# Tay_Cam.net
KiCad netlist of a schematic drawn in Altium Designer
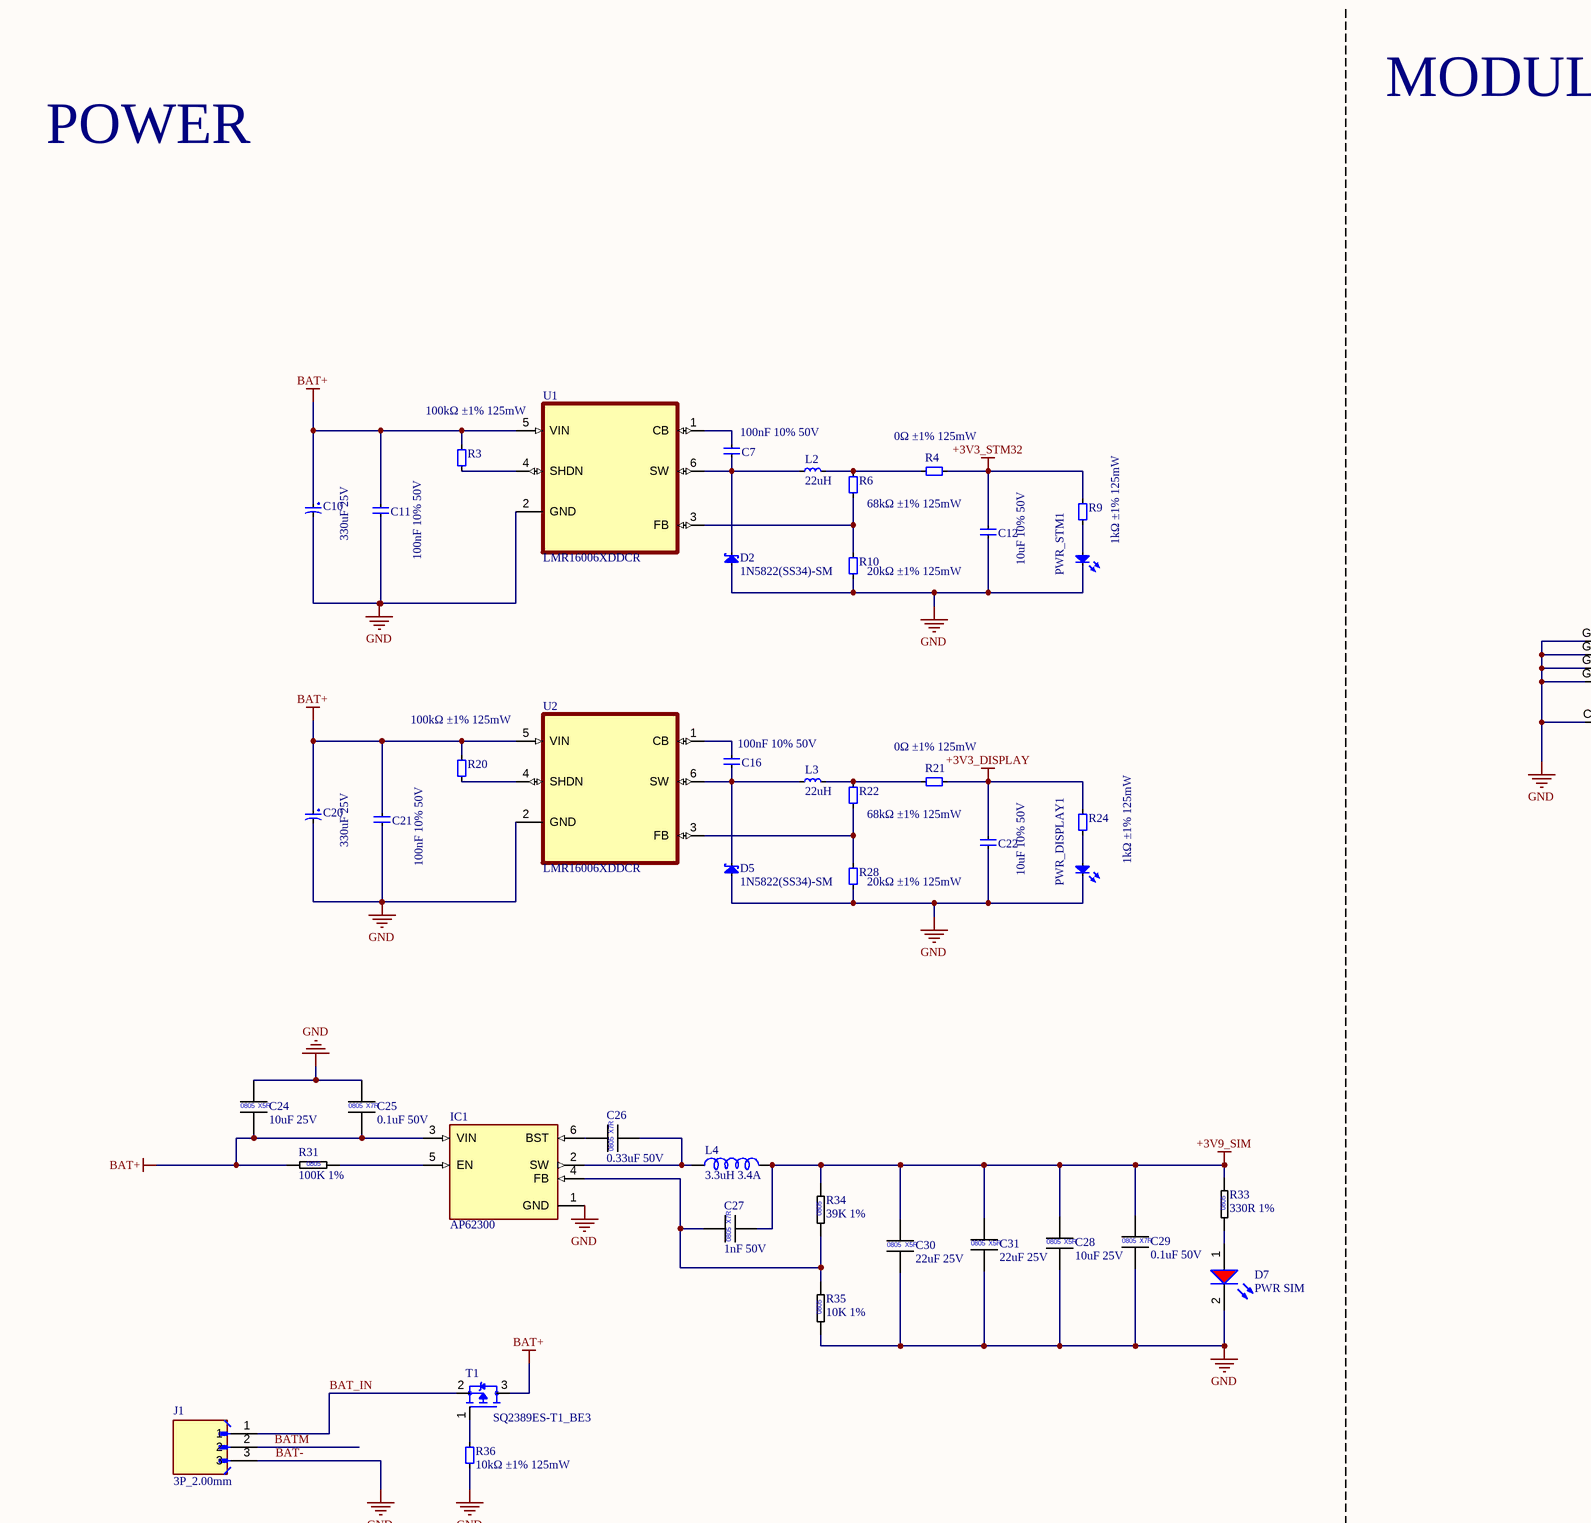
[diagram p0: Tay_Cam.SchDoc, top column 1 of 4]
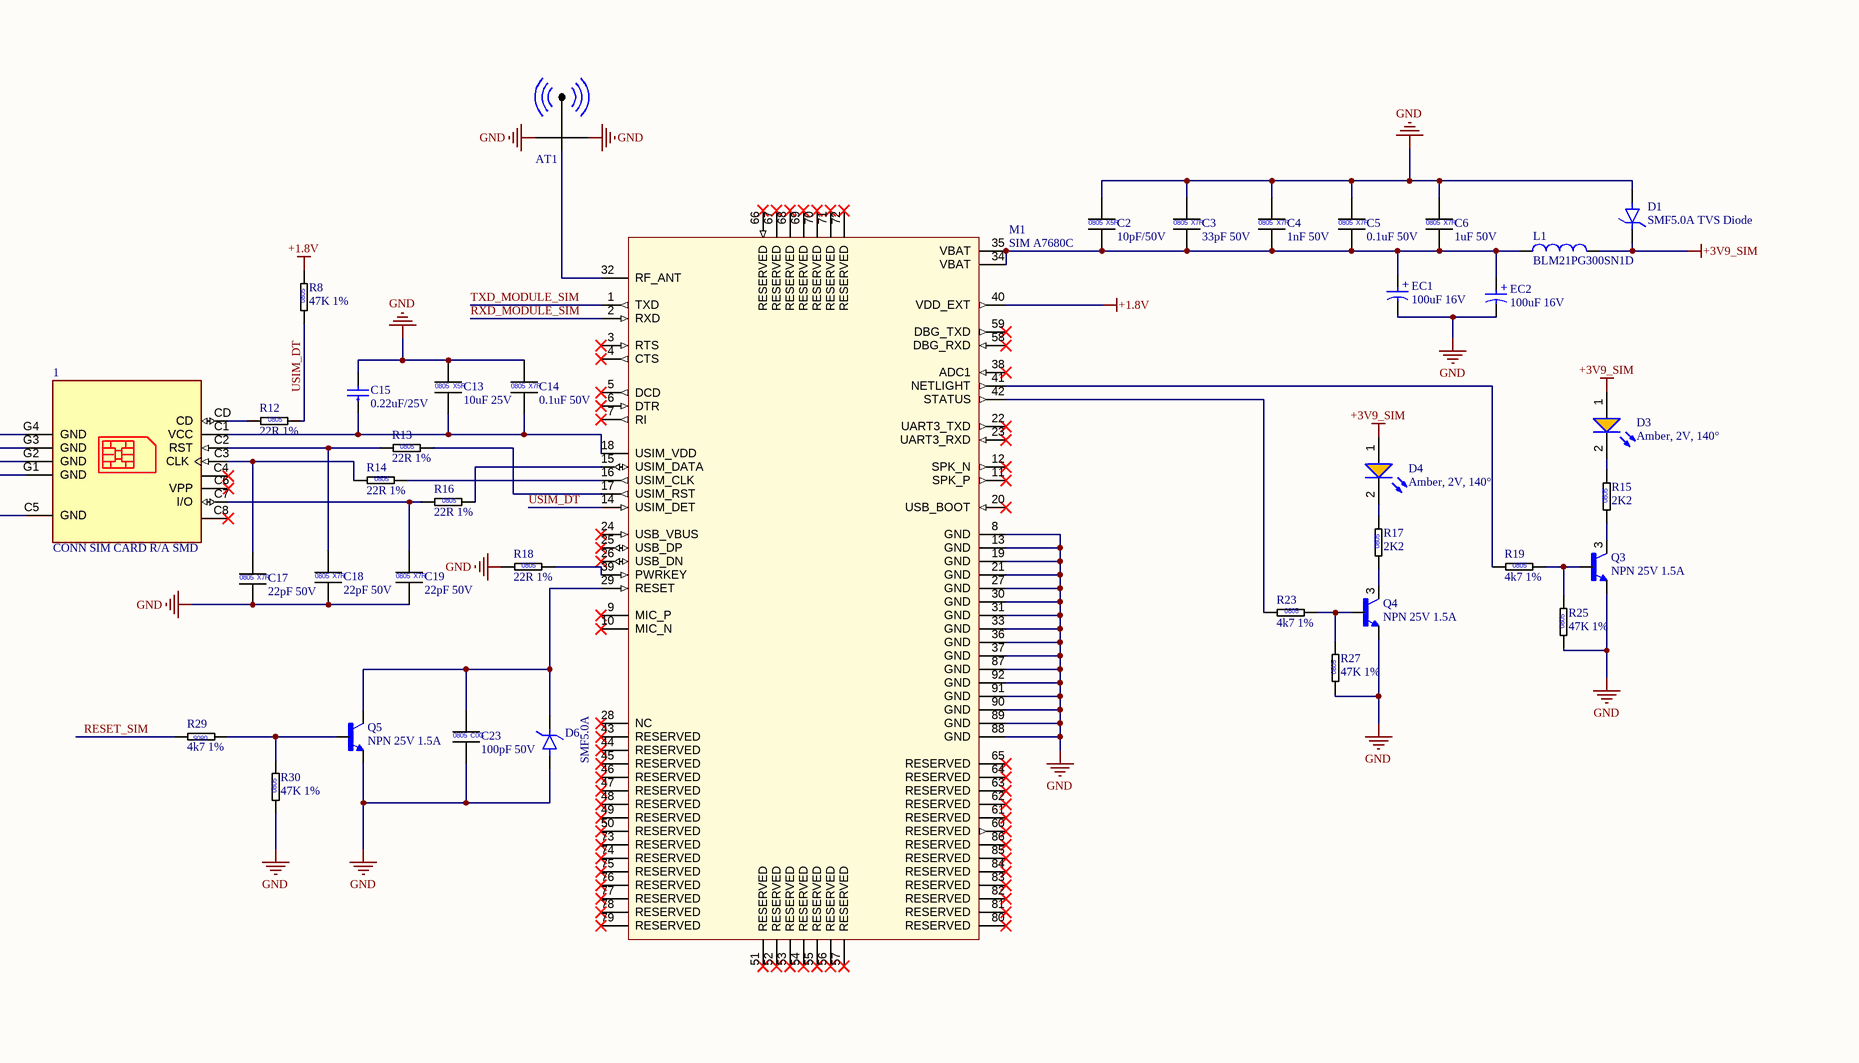
[diagram p1: Tay_Cam.SchDoc, top column 2 of 4]
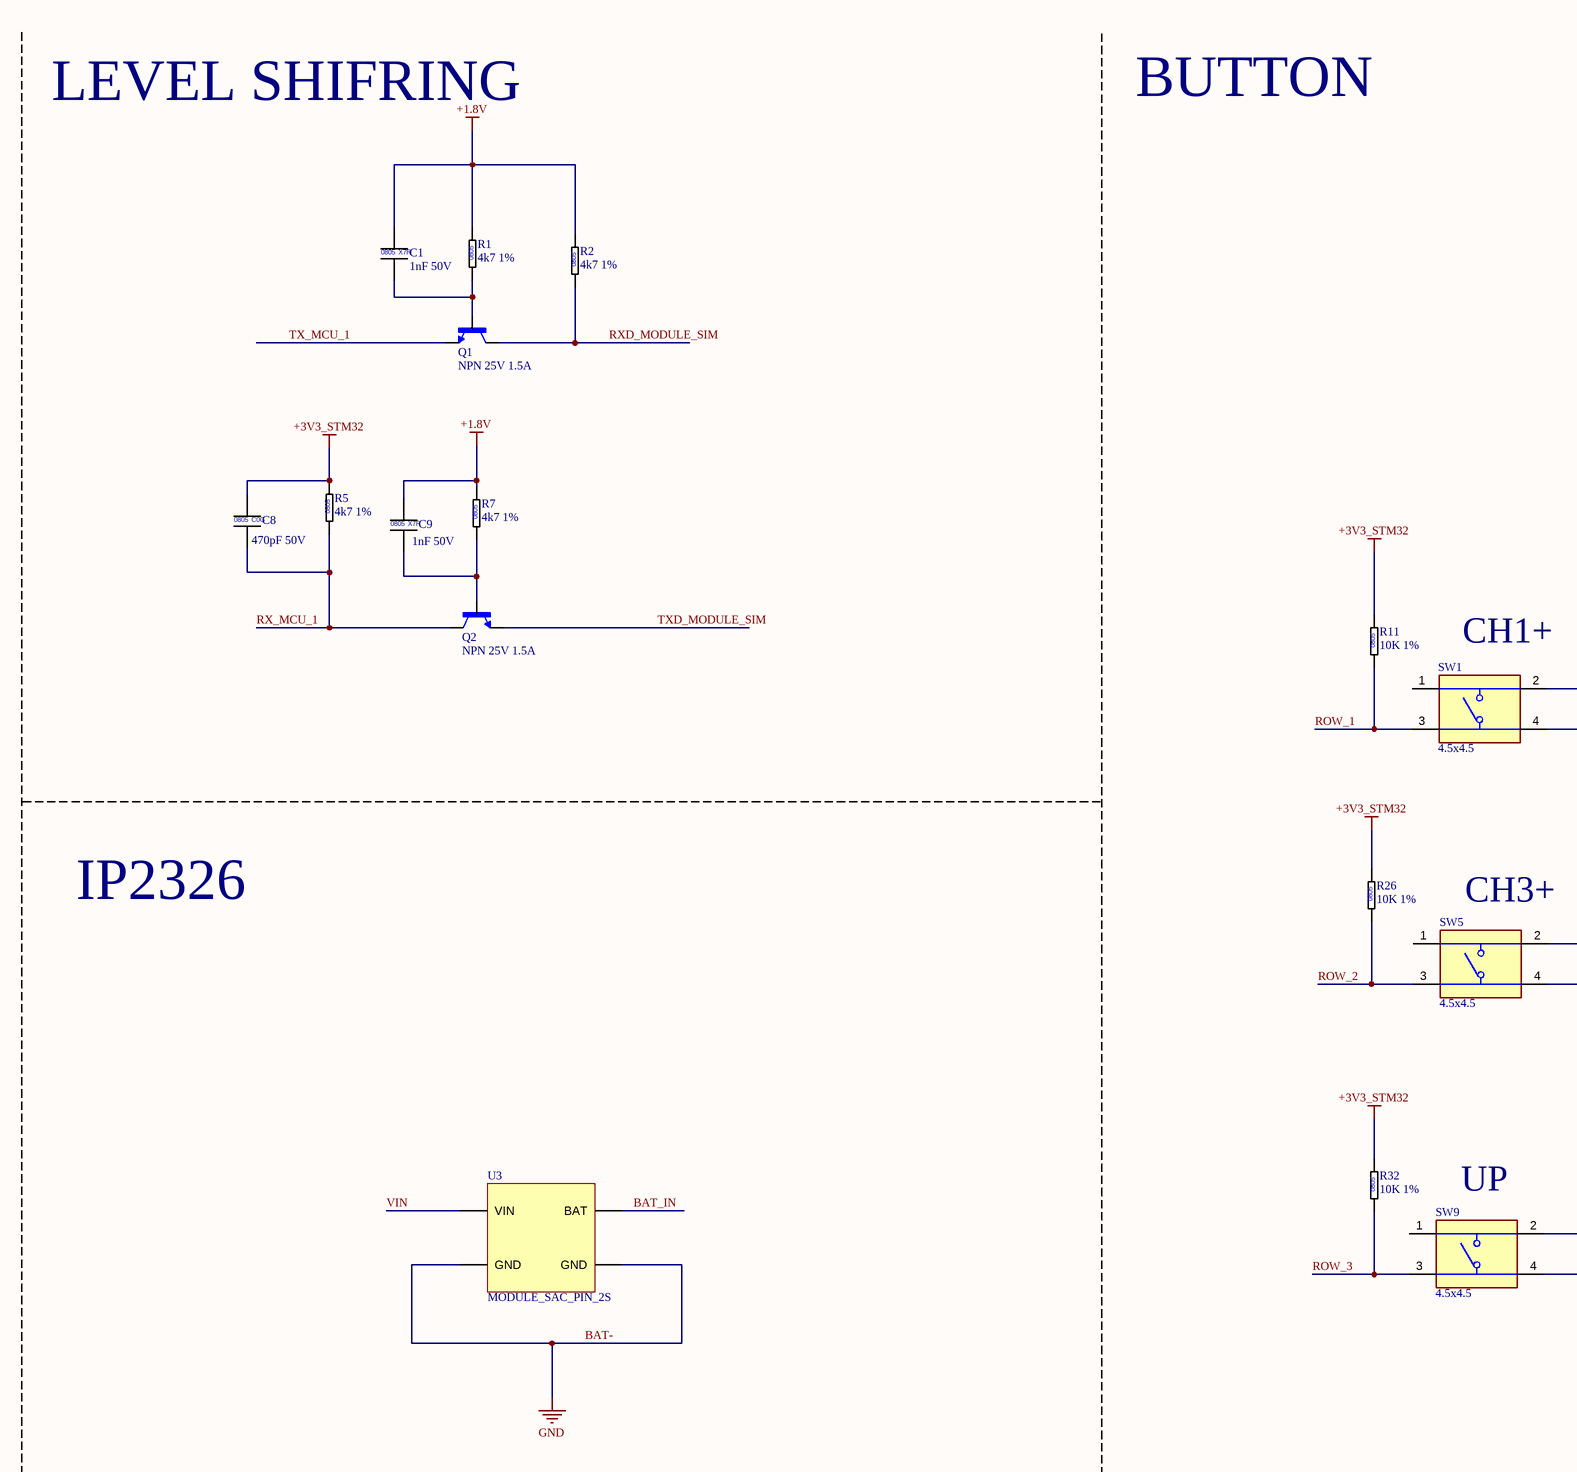
[diagram p2: Tay_Cam.SchDoc, top column 3 of 4]
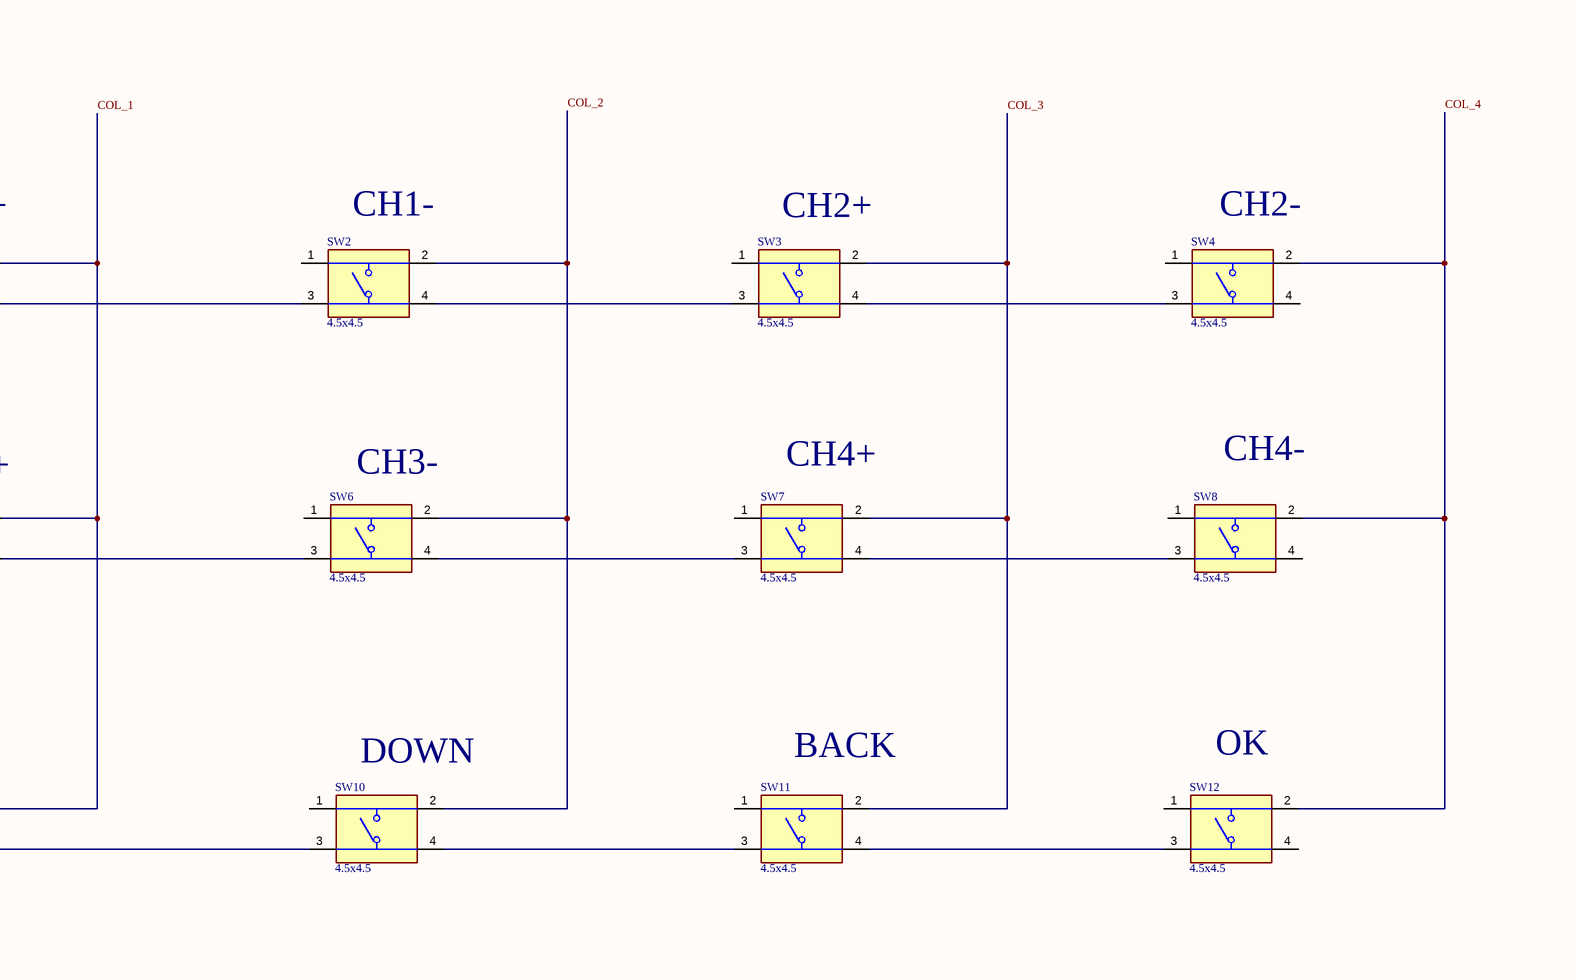
[diagram p3: Tay_Cam.SchDoc, top column 4 of 4]
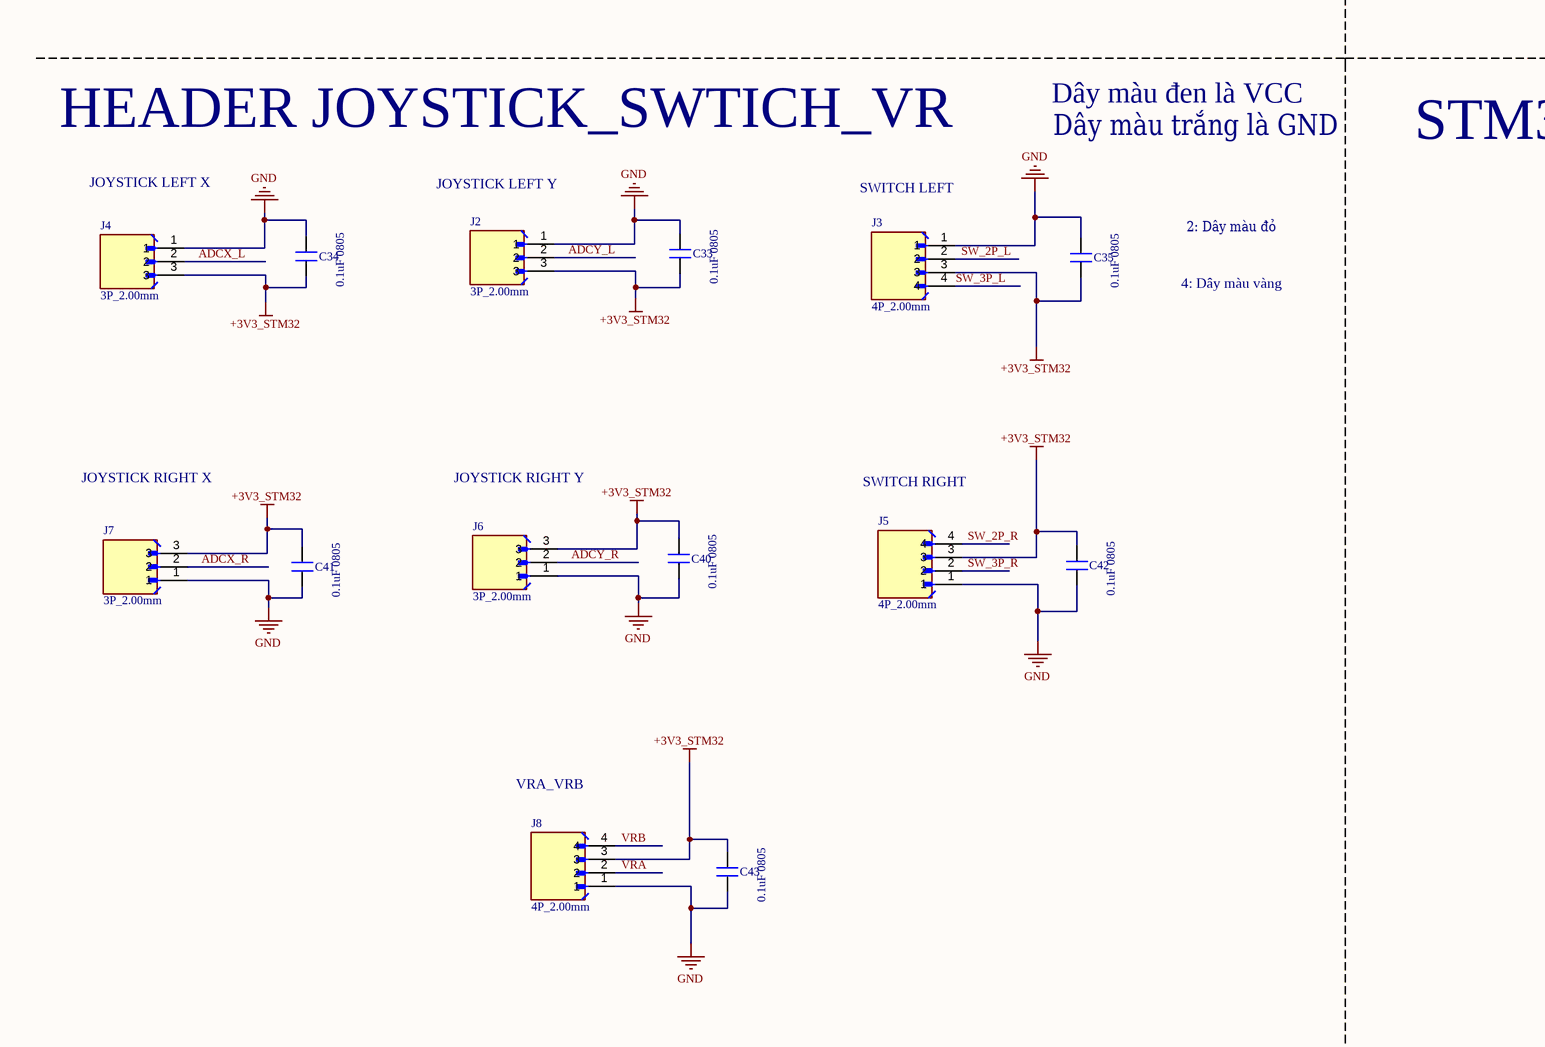
[diagram p4: Tay_Cam.SchDoc, bottom column 1 of 4]
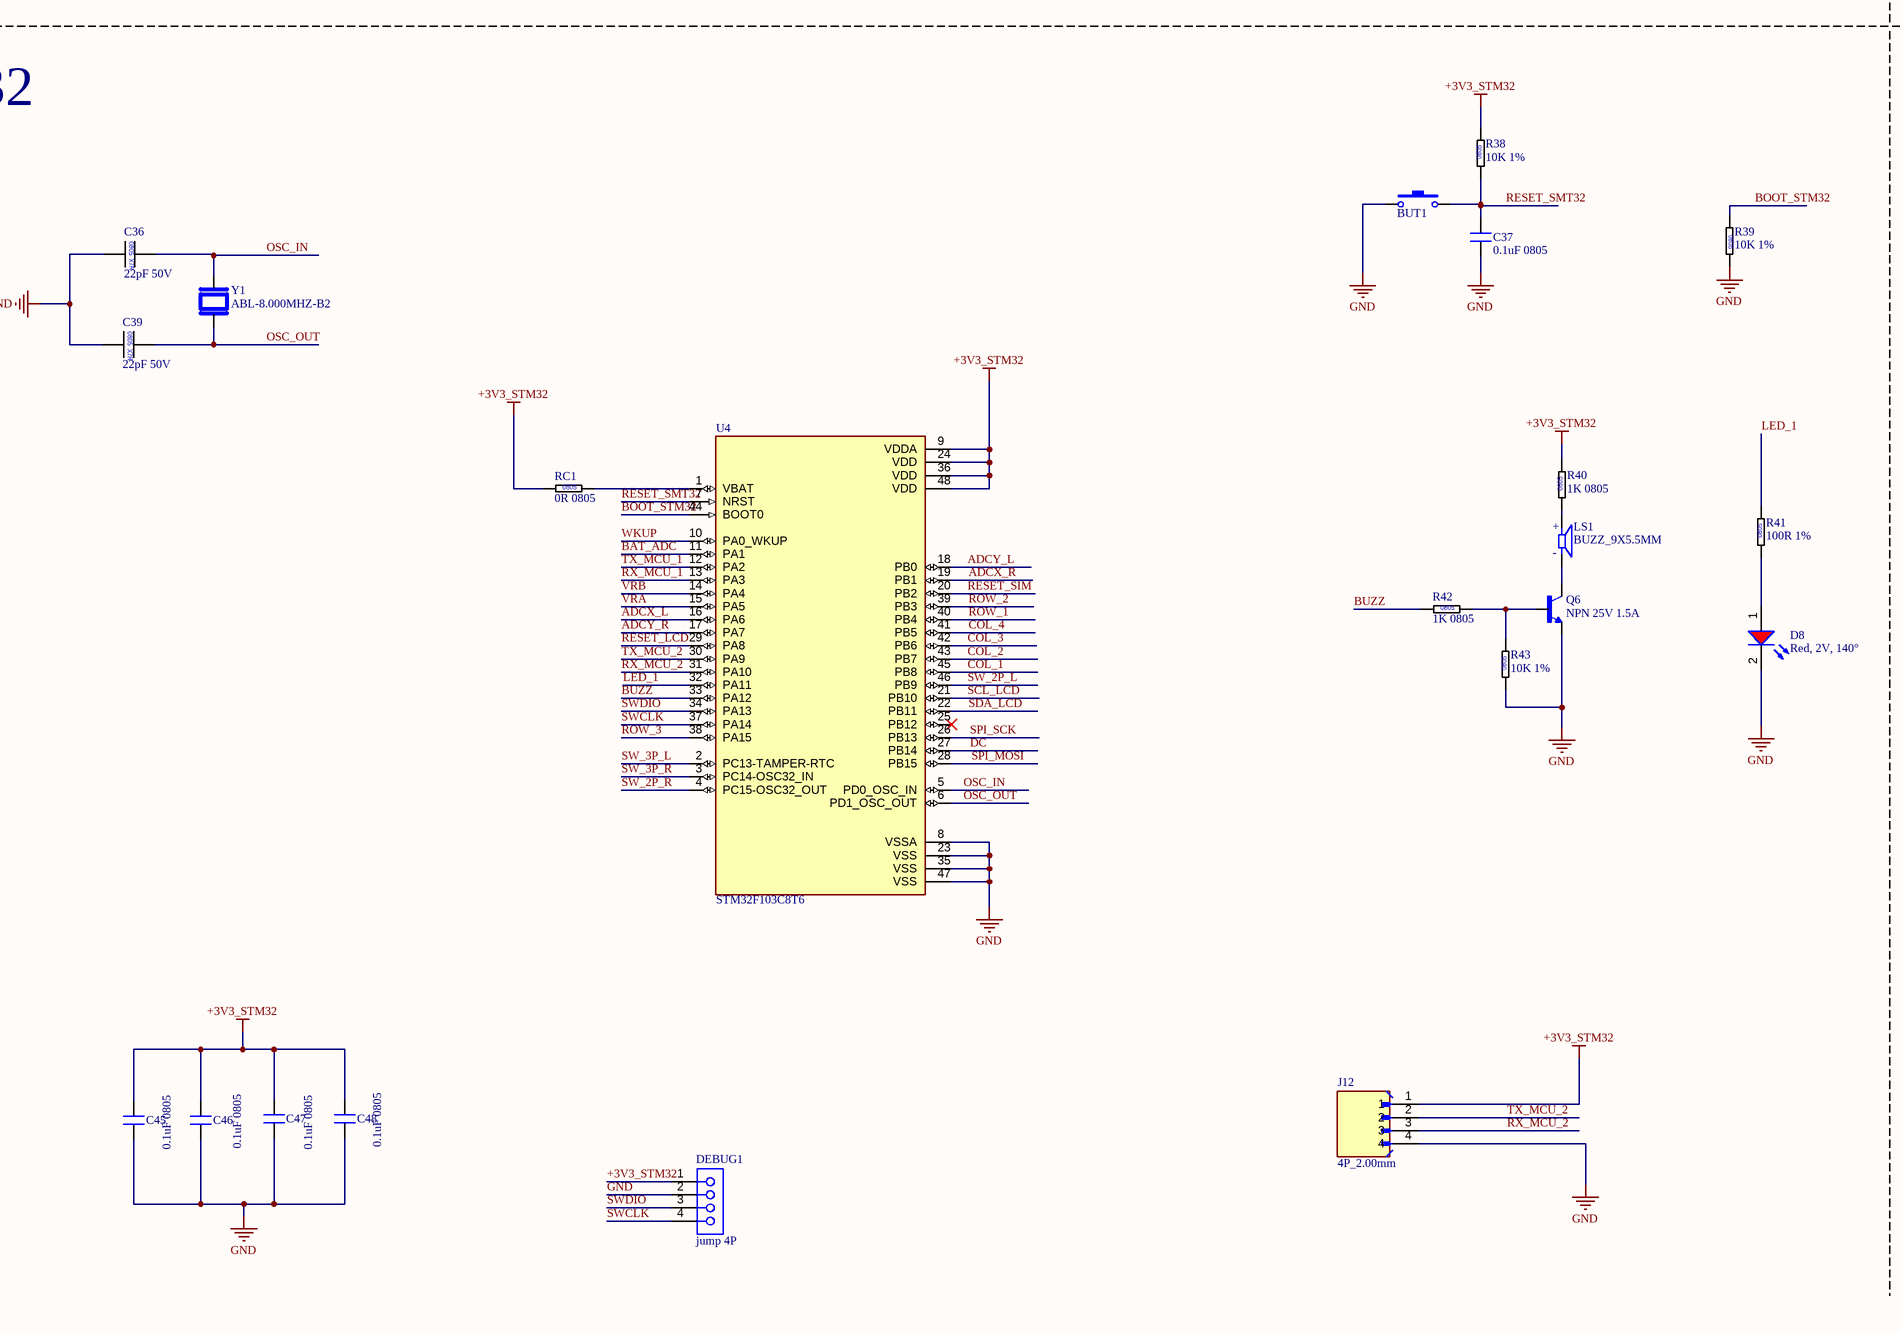
[diagram p5: Tay_Cam.SchDoc, bottom column 2 of 4]
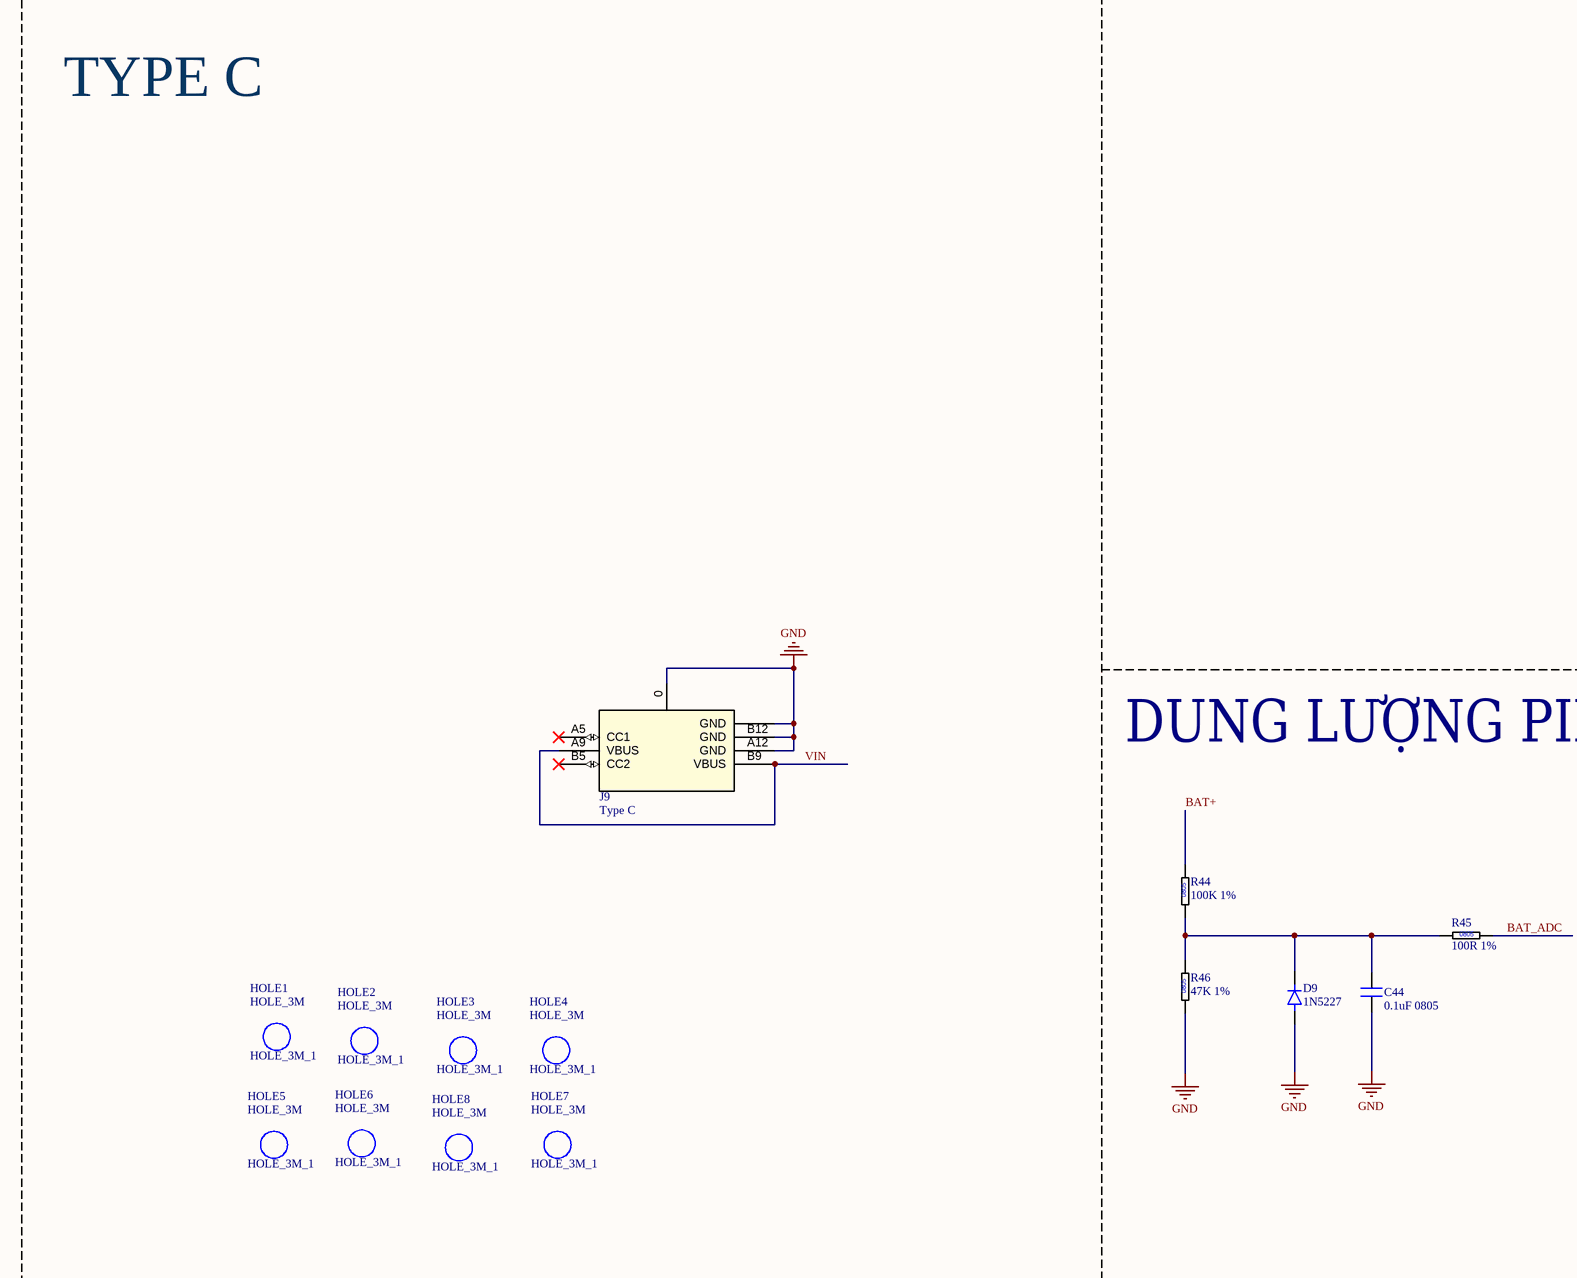
[diagram p6: Tay_Cam.SchDoc, bottom column 3 of 4]
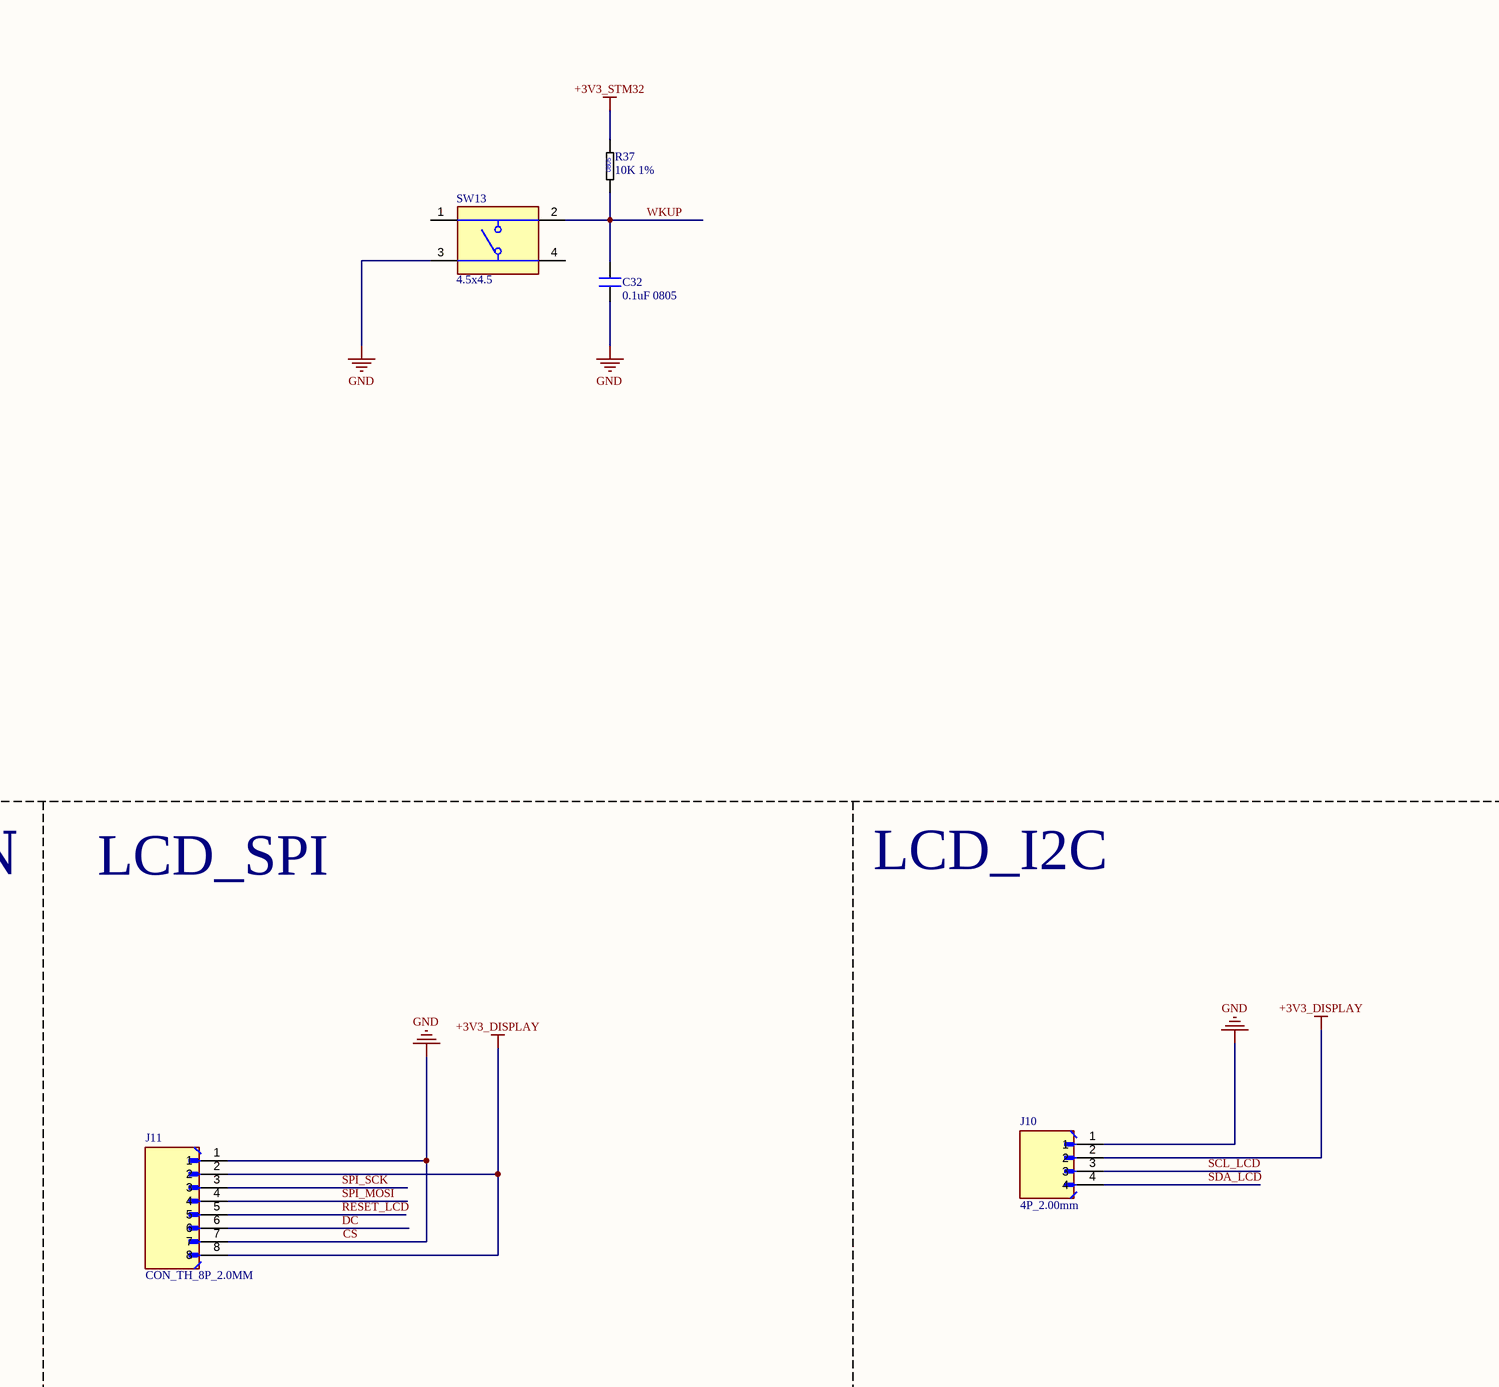
[diagram p7: Tay_Cam.SchDoc, bottom column 4 of 4]

(export (version "E")
  (design (tool "Eeschema 10.0.6"))
  (components
    (comp (ref "1")
      (value "CONN SIM CARD R/A SMD")
      (footprint "SIM HOLDER 9P")
      (description "8 (6 + 2) Position Card Connector SIM Card Surface Mount, Right Angle Gold")
      (fields
        (field (name "MANUFACTURER") "Molex")
        (field (name "MANUFACTURER PART NUMBER") "0475532001")
        (field (name "LIBRARY MADE BY") "MR. XUAN SIEU")
      )
      (libsource (lib "SIM_A7680C") (part "CONN_SIM HOLDER 9P"))
    )
    (comp (ref "AT1")
      (value "Antenna_IPEX")
      (footprint "IPEX")
      (description "Antenna")
      (libsource (lib "PCB_NODE_2") (part "Antenna_IPEX"))
    )
    (comp (ref "BUT1")
      (value "Nut Nhan 2 Chan SMD 3x6x2.5")
      (footprint "Nut Nhan 2 Chan SMD 3x6x2.5")
      (libsource (lib "LIBRARY2026") (part "Nut Nhan 2 Chan SMD 3x6x2.5"))
    )
    (comp (ref "C1")
      (value "1nF 50V")
      (footprint "CAP-CER_0805_L2W1.25H0.6_Wave")
      (description "1000 pF (102,1nF) ±10% 50V Ceramic Capacitor X7R 0805 (2012 Metric),")
      (fields
        (field (name "MANUFACTURER PART NUMBER") "C0805C102K5RACTU")
        (field (name "TOLERANCE") "10%")
        (field (name "LIBRARY MADE BY") "MR. XUAN SIEU")
      )
      (libsource (lib "SIM_A7680C") (part "CAP_CER_SMD; 1000PF 50V X7R 0805 10%"))
    )
    (comp (ref "C2")
      (value "10pF/50V")
      (footprint "CAP-CER_0805_L2W1.25H0.6_Wave")
      (description "Cap Ceramic 10pF 50V C0G 0.25pF Pad SMD 0805 125°C T/R")
      (fields
        (field (name "MANUFACTURER") "Samsung Electro-Mechanics")
        (field (name "MANUFACTURER PART NUMBER") "CL21C100CBANNNC")
        (field (name "LIBRARY MADE BY") "MR. XUAN SIEU")
      )
      (libsource (lib "SIM_A7680C") (part "CAP_CER_SMD; 10PF 50V C0G/NP0 0805 2.5%"))
    )
    (comp (ref "C3")
      (value "33pF 50V")
      (footprint "CAP-CER_0805_L2W1.25H0.6_Wave")
      (description "Cap Ceramic 33pF (330) 50V C0G 10% SMD 0805 125C Paper T/R")
      (fields
        (field (name "MANUFACTURER PART NUMBER") "C0805C330K5GACTU")
        (field (name "TOLERANCE") "10%")
        (field (name "LIBRARY MADE BY") "MR. XUAN SIEU")
      )
      (libsource (lib "SIM_A7680C") (part "CAP_CER_SMD; 33PF 50V C0G/NP0 0805 10%"))
    )
    (comp (ref "C4")
      (value "1nF 50V")
      (footprint "CAP-CER_0805_L2W1.25H0.6_Wave")
      (description "1000 pF (102,1nF) ±10% 50V Ceramic Capacitor X7R 0805 (2012 Metric),")
      (fields
        (field (name "MANUFACTURER PART NUMBER") "C0805C102K5RACTU")
        (field (name "TOLERANCE") "10%")
        (field (name "LIBRARY MADE BY") "MR. XUAN SIEU")
      )
      (libsource (lib "SIM_A7680C") (part "CAP_CER_SMD; 1000PF 50V X7R 0805 10%"))
    )
    (comp (ref "C5")
      (value "0.1uF 50V")
      (footprint "CAP-CER_0805_L2W1.25H0.6_Wave")
      (description "0.1 (104) µF ±10% 50V Ceramic Capacitor X7R 0805 (2012 Metric)")
      (fields
        (field (name "MANUFACTURER PART NUMBER") "CC0805KRX7R9BB104")
        (field (name "TOLERANCE") "10%")
        (field (name "LIBRARY MADE BY") "MR. XUAN SIEU")
      )
      (libsource (lib "SIM_A7680C") (part "CAP_CER_SMD; 0.1UF 50V X7R 0805 10%"))
    )
    (comp (ref "C6")
      (value "1uF 50V")
      (footprint "CAP-CER_0805_L2W1.25H0.8_Wave")
      (description "Cap Ceramic 1uF 50V X7R 10% SMD 0805 125°C Embossed Plastic T/R")
      (fields
        (field (name "MANUFACTURER PART NUMBER") "CL21B105KBFNNNG")
        (field (name "TOLERANCE") "10%")
        (field (name "LIBRARY MADE BY") "MR. XUAN SIEU")
      )
      (libsource (lib "SIM_A7680C") (part "CAP_CER_SMD; 1UF 50V X7R 0805 10%"))
    )
    (comp (ref "C7")
      (value "100nF 10% 50V")
      (footprint "C-CHIP-0805-T0.95-SM")
      (description "X7R 100nF 50V ±10% 0603 Multilayer Ceramic Capacitors MLCC - SMD/SMT ROHS")
      (fields (field (name "MANUFACTURER") "YAGEO") (field (name "USER") "1"))
      (libsource (lib "PCB_NODE_2") (part "C-SM"))
    )
    (comp (ref "C8")
      (value "470pF 50V")
      (footprint "CAP-CER_0805_L2W1.25H0.6_Wave")
      (description "470 pF ±5% 50V Ceramic Capacitor C0G, NP0 0805 (2012 Metric)")
      (fields
        (field (name "MANUFACTURER") "Wurth Elektronik")
        (field (name "MANUFACTURER PART NUMBER") "885012007061")
      )
      (libsource (lib "SIM_A7680C") (part "CAP_CER_SMD; 470PF 50V C0G/NP0 0805 5%"))
    )
    (comp (ref "C9")
      (value "1nF 50V")
      (footprint "CAP-CER_0805_L2W1.25H0.6_Wave")
      (description "1000 pF (102,1nF) ±10% 50V Ceramic Capacitor X7R 0805 (2012 Metric),")
      (fields
        (field (name "MANUFACTURER PART NUMBER") "C0805C102K5RACTU")
        (field (name "TOLERANCE") "10%")
        (field (name "LIBRARY MADE BY") "MR. XUAN SIEU")
      )
      (libsource (lib "SIM_A7680C") (part "CAP_CER_SMD; 1000PF 50V X7R 0805 10%"))
    )
    (comp (ref "C10")
      (value "330uF 25V")
      (footprint "C-ELEC-ALU-F-D8.0-H10.2-SM")
      (description "Aluminum Electrolytic Capacitors - Surface Mount")
      (libsource (lib "PCB_NODE_2") (part "C-ELEC-ALU-SM"))
    )
    (comp (ref "C11")
      (value "100nF 10% 50V")
      (footprint "C-CHIP-0805-T0.95-SM")
      (description "X7R 100nF 50V ±10% 0603 Multilayer Ceramic Capacitors MLCC - SMD/SMT ROHS")
      (fields (field (name "MANUFACTURER") "YAGEO") (field (name "USER") "1"))
      (libsource (lib "PCB_NODE_2") (part "C-SM"))
    )
    (comp (ref "C12")
      (value "10uF 10% 50V")
      (footprint "C-CHIP-1206-T1.00-SM")
      (description "X7R 100nF 50V ±10% 0603 Multilayer Ceramic Capacitors MLCC - SMD/SMT ROHS")
      (fields (field (name "MANUFACTURER") "YAGEO") (field (name "USER") "1"))
      (libsource (lib "PCB_NODE_2") (part "C-SM_1"))
    )
    (comp (ref "C13")
      (value "10uF 25V")
      (footprint "CAP-CER_0805_L2W1.25H0.8_Wave")
      (description "10 µF ±10% 25V Ceramic Capacitor X5R 0805 (2012 Metric)")
      (fields
        (field (name "MANUFACTURER PART NUMBER") "GRM21BR61E106KA73L")
        (field (name "TOLERANCE") "10%")
        (field (name "LIBRARY MADE BY") "MR. XUAN SIEU")
      )
      (libsource (lib "SIM_A7680C") (part "CAP_CER_SMD; 10UF 25V X5R 0805 10%"))
    )
    (comp (ref "C14")
      (value "0.1uF 50V")
      (footprint "CAP-CER_0805_L2W1.25H0.6_Wave")
      (description "0.1 (104) µF ±10% 50V Ceramic Capacitor X7R 0805 (2012 Metric)")
      (fields
        (field (name "MANUFACTURER PART NUMBER") "CC0805KRX7R9BB104")
        (field (name "TOLERANCE") "10%")
        (field (name "LIBRARY MADE BY") "MR. XUAN SIEU")
      )
      (libsource (lib "SIM_A7680C") (part "CAP_CER_SMD; 0.1UF 50V X7R 0805 10%"))
    )
    (comp (ref "C15")
      (value "0.22uF/25V")
      (footprint "CAP-CER0805-1.4H")
      (description "CAP CER 0.22uF/25V 10% X7R 0805 SMD")
      (libsource (lib "SIM_A7680C") (part "CAPCER0094 0805 0.22uF/25V 220nF"))
    )
    (comp (ref "C16")
      (value "100nF 10% 50V")
      (footprint "C-CHIP-0805-T0.95-SM")
      (description "X7R 100nF 50V ±10% 0603 Multilayer Ceramic Capacitors MLCC - SMD/SMT ROHS")
      (fields (field (name "MANUFACTURER") "YAGEO") (field (name "USER") "1"))
      (libsource (lib "PCB_NODE_2") (part "C-SM"))
    )
    (comp (ref "C17")
      (value "22pF 50V")
      (footprint "CAP-CER_0805_L2W1.25H0.6_Wave")
      (fields
        (field (name "MANUFACTURER PART NUMBER") "C0805C220J5GACTU")
        (field (name "TOLERANCE") "5%")
        (field (name "VOLTAGE") "50V")
        (field (name "LIBRARY MADE BY") "MR. XUAN SIEU")
      )
      (libsource (lib "SIM_A7680C") (part "CAP_CER_SMD; 22PF 50V C0G/NP0 0805 5%"))
    )
    (comp (ref "C18")
      (value "22pF 50V")
      (footprint "CAP-CER_0805_L2W1.25H0.6_Wave")
      (fields
        (field (name "MANUFACTURER PART NUMBER") "C0805C220J5GACTU")
        (field (name "TOLERANCE") "5%")
        (field (name "VOLTAGE") "50V")
        (field (name "LIBRARY MADE BY") "MR. XUAN SIEU")
      )
      (libsource (lib "SIM_A7680C") (part "CAP_CER_SMD; 22PF 50V C0G/NP0 0805 5%"))
    )
    (comp (ref "C19")
      (value "22pF 50V")
      (footprint "CAP-CER_0805_L2W1.25H0.6_Wave")
      (fields
        (field (name "MANUFACTURER PART NUMBER") "C0805C220J5GACTU")
        (field (name "TOLERANCE") "5%")
        (field (name "VOLTAGE") "50V")
        (field (name "LIBRARY MADE BY") "MR. XUAN SIEU")
      )
      (libsource (lib "SIM_A7680C") (part "CAP_CER_SMD; 22PF 50V C0G/NP0 0805 5%"))
    )
    (comp (ref "C20")
      (value "330uF 25V")
      (footprint "C-ELEC-ALU-F-D8.0-H10.2-SM")
      (description "Aluminum Electrolytic Capacitors - Surface Mount")
      (libsource (lib "PCB_NODE_2") (part "C-ELEC-ALU-SM"))
    )
    (comp (ref "C21")
      (value "100nF 10% 50V")
      (footprint "C-CHIP-0805-T0.95-SM")
      (description "X7R 100nF 50V ±10% 0603 Multilayer Ceramic Capacitors MLCC - SMD/SMT ROHS")
      (fields (field (name "MANUFACTURER") "YAGEO") (field (name "USER") "1"))
      (libsource (lib "PCB_NODE_2") (part "C-SM"))
    )
    (comp (ref "C22")
      (value "10uF 10% 50V")
      (footprint "C-CHIP-1206-T1.00-SM")
      (description "X7R 100nF 50V ±10% 0603 Multilayer Ceramic Capacitors MLCC - SMD/SMT ROHS")
      (fields (field (name "MANUFACTURER") "YAGEO") (field (name "USER") "1"))
      (libsource (lib "PCB_NODE_2") (part "C-SM_1"))
    )
    (comp (ref "C23")
      (value "100pF 50V")
      (footprint "CAP-CER_0805_L2W1.25H0.6_Wave")
      (description "100 pF ±5% 50V Ceramic Capacitor C0G, NP0 0805 (2012 Metric)")
      (fields
        (field (name "MANUFACTURER PART NUMBER") "CL21C101JBANNNC")
        (field (name "LIBRARY MADE BY") "MR. XUAN SIEU")
      )
      (libsource (lib "SIM_A7680C") (part "CAP_CER_SMD; 100PF 50V C0G/NP0 0805 10%"))
    )
    (comp (ref "C24")
      (value "10uF 25V")
      (footprint "CAP-CER_0805_L2W1.25H0.8_Wave")
      (description "10 µF ±10% 25V Ceramic Capacitor X5R 0805 (2012 Metric)")
      (fields
        (field (name "MANUFACTURER PART NUMBER") "GRM21BR61E106KA73L")
        (field (name "TOLERANCE") "10%")
        (field (name "LIBRARY MADE BY") "MR. XUAN SIEU")
      )
      (libsource (lib "PWR_3V3_5V_3V9") (part "CAP_CER_SMD; 10UF 25V X5R 0805 10%"))
    )
    (comp (ref "C25")
      (value "0.1uF 50V")
      (footprint "CAP-CER_0805_L2W1.25H0.6_Wave")
      (description "0.1 (104) µF ±10% 50V Ceramic Capacitor X7R 0805 (2012 Metric)")
      (fields
        (field (name "MANUFACTURER PART NUMBER") "CC0805KRX7R9BB104")
        (field (name "TOLERANCE") "10%")
        (field (name "LIBRARY MADE BY") "MR. XUAN SIEU")
      )
      (libsource (lib "PWR_3V3_5V_3V9") (part "CAP_CER_SMD; 0.1UF 50V X7R 0805 10%"))
    )
    (comp (ref "C26")
      (value "0.33uF 50V")
      (footprint "CAP-CER_0805_L2W1.25H0.6_Wave")
      (description "0.33 µF ±10% 50V Ceramic Capacitor X7R 0805 (2012 Metric)")
      (fields
        (field (name "MANUFACTURER") "Wurth Electronics")
        (field (name "MANUFACTURER PART NUMBER") "885012207101")
        (field (name "LIBRARY MADE BY") "MR. XUAN SIEU")
      )
      (libsource (lib "PWR_3V3_5V_3V9") (part "CAP_CER_SMD; 0.33UF 50V X7R 0805 10%"))
    )
    (comp (ref "C27")
      (value "1nF 50V")
      (footprint "CAP-CER_0805_L2W1.25H0.6_Wave")
      (description "1000 pF (102,1nF) ±10% 50V Ceramic Capacitor X7R 0805 (2012 Metric),")
      (fields
        (field (name "MANUFACTURER PART NUMBER") "C0805C102K5RACTU")
        (field (name "TOLERANCE") "10%")
        (field (name "LIBRARY MADE BY") "MR. XUAN SIEU")
      )
      (libsource (lib "PWR_3V3_5V_3V9") (part "CAP_CER_SMD; 1000PF 50V X7R 0805 10%"))
    )
    (comp (ref "C28")
      (value "10uF 25V")
      (footprint "CAP-CER_0805_L2W1.25H0.8_Wave")
      (description "10 µF ±10% 25V Ceramic Capacitor X5R 0805 (2012 Metric)")
      (fields
        (field (name "MANUFACTURER PART NUMBER") "GRM21BR61E106KA73L")
        (field (name "TOLERANCE") "10%")
        (field (name "LIBRARY MADE BY") "MR. XUAN SIEU")
      )
      (libsource (lib "PWR_3V3_5V_3V9") (part "CAP_CER_SMD; 10UF 25V X5R 0805 10%"))
    )
    (comp (ref "C29")
      (value "0.1uF 50V")
      (footprint "CAP-CER_0805_L2W1.25H0.6_Wave")
      (description "0.1 (104) µF ±10% 50V Ceramic Capacitor X7R 0805 (2012 Metric)")
      (fields
        (field (name "MANUFACTURER PART NUMBER") "CC0805KRX7R9BB104")
        (field (name "TOLERANCE") "10%")
        (field (name "LIBRARY MADE BY") "MR. XUAN SIEU")
      )
      (libsource (lib "PWR_3V3_5V_3V9") (part "CAP_CER_SMD; 0.1UF 50V X7R 0805 10%"))
    )
    (comp (ref "C30")
      (value "22uF 25V")
      (footprint "CAP-CER_0805_L2W1.25H0.6_Wave")
      (description "25V 22uF X5R ±20% 0805 Multilayer Ceramic Capacitors MLCC - SMD/SMT ROHS")
      (fields
        (field (name "MANUFACTURER") "Samsung Electro-Mechanics")
        (field (name "MANUFACTURER PART NUMBER") "CL21A226MAYNNNE")
      )
      (libsource (lib "PWR_3V3_5V_3V9") (part "CAP_CER_SMD; 22UF 25V X5R 0805 20%"))
    )
    (comp (ref "C31")
      (value "22uF 25V")
      (footprint "CAP-CER_0805_L2W1.25H0.6_Wave")
      (description "25V 22uF X5R ±20% 0805 Multilayer Ceramic Capacitors MLCC - SMD/SMT ROHS")
      (fields
        (field (name "MANUFACTURER") "Samsung Electro-Mechanics")
        (field (name "MANUFACTURER PART NUMBER") "CL21A226MAYNNNE")
      )
      (libsource (lib "PWR_3V3_5V_3V9") (part "CAP_CER_SMD; 22UF 25V X5R 0805 20%"))
    )
    (comp (ref "C32")
      (value "0.1uF 0805")
      (footprint "CAP-CER_0603_L1.6W0.8H0.8_Wave")
      (description "0.1 (104) µF ±10% 50V Ceramic Capacitor X7R 0805 (2012 Metric)")
      (fields
        (field (name "MANUFACTURER PART NUMBER") "CC0805KRX7R9BB104")
        (field (name "TOLERANCE") "10%")
        (field (name "LIBRARY MADE BY") "MR. XUAN SIEU")
      )
      (libsource (lib "LIBRARY2026") (part "CAP_CER,SMD;0.1uF,10%,0805,50V,X7R"))
    )
    (comp (ref "C33")
      (value "0.1uF 0805")
      (footprint "CAP-CER_0603_L1.6W0.8H0.8_Wave")
      (description "0.1 (104) µF ±10% 50V Ceramic Capacitor X7R 0805 (2012 Metric)")
      (fields
        (field (name "MANUFACTURER PART NUMBER") "CC0805KRX7R9BB104")
        (field (name "TOLERANCE") "10%")
        (field (name "LIBRARY MADE BY") "MR. XUAN SIEU")
      )
      (libsource (lib "LIBRARY2026") (part "CAP_CER,SMD;0.1uF,10%,0805,50V,X7R"))
    )
    (comp (ref "C34")
      (value "0.1uF 0805")
      (footprint "CAP-CER_0603_L1.6W0.8H0.8_Wave")
      (description "0.1 (104) µF ±10% 50V Ceramic Capacitor X7R 0805 (2012 Metric)")
      (fields
        (field (name "MANUFACTURER PART NUMBER") "CC0805KRX7R9BB104")
        (field (name "TOLERANCE") "10%")
        (field (name "LIBRARY MADE BY") "MR. XUAN SIEU")
      )
      (libsource (lib "LIBRARY2026") (part "CAP_CER,SMD;0.1uF,10%,0805,50V,X7R"))
    )
    (comp (ref "C35")
      (value "0.1uF 0805")
      (footprint "CAP-CER_0603_L1.6W0.8H0.8_Wave")
      (description "0.1 (104) µF ±10% 50V Ceramic Capacitor X7R 0805 (2012 Metric)")
      (fields
        (field (name "MANUFACTURER PART NUMBER") "CC0805KRX7R9BB104")
        (field (name "TOLERANCE") "10%")
        (field (name "LIBRARY MADE BY") "MR. XUAN SIEU")
      )
      (libsource (lib "LIBRARY2026") (part "CAP_CER,SMD;0.1uF,10%,0805,50V,X7R"))
    )
    (comp (ref "C36")
      (value "22pF 50V")
      (footprint "CAP-CER_0805_L2W1.25H0.6_Wave")
      (fields
        (field (name "MANUFACTURER PART NUMBER") "C0805C220J5GACTU")
        (field (name "TOLERANCE") "5%")
        (field (name "VOLTAGE") "50V")
        (field (name "LIBRARY MADE BY") "MR. XUAN SIEU")
      )
      (libsource (lib "LIBRARY2026") (part "CAP_CER_SMD; 22PF 50V C0G/NP0 0805 5%"))
    )
    (comp (ref "C37")
      (value "0.1uF 0805")
      (footprint "CAP-CER_0603_L1.6W0.8H0.8_Wave")
      (description "0.1 (104) µF ±10% 50V Ceramic Capacitor X7R 0805 (2012 Metric)")
      (fields
        (field (name "MANUFACTURER PART NUMBER") "CC0805KRX7R9BB104")
        (field (name "TOLERANCE") "10%")
        (field (name "LIBRARY MADE BY") "MR. XUAN SIEU")
      )
      (libsource (lib "LIBRARY2026") (part "CAP_CER,SMD;0.1uF,10%,0805,50V,X7R"))
    )
    (comp (ref "C39")
      (value "22pF 50V")
      (footprint "CAP-CER_0805_L2W1.25H0.6_Wave")
      (fields
        (field (name "MANUFACTURER PART NUMBER") "C0805C220J5GACTU")
        (field (name "TOLERANCE") "5%")
        (field (name "VOLTAGE") "50V")
        (field (name "LIBRARY MADE BY") "MR. XUAN SIEU")
      )
      (libsource (lib "LIBRARY2026") (part "CAP_CER_SMD; 22PF 50V C0G/NP0 0805 5%"))
    )
    (comp (ref "C40")
      (value "0.1uF 0805")
      (footprint "CAP-CER_0603_L1.6W0.8H0.8_Wave")
      (description "0.1 (104) µF ±10% 50V Ceramic Capacitor X7R 0805 (2012 Metric)")
      (fields
        (field (name "MANUFACTURER PART NUMBER") "CC0805KRX7R9BB104")
        (field (name "TOLERANCE") "10%")
        (field (name "LIBRARY MADE BY") "MR. XUAN SIEU")
      )
      (libsource (lib "LIBRARY2026") (part "CAP_CER,SMD;0.1uF,10%,0805,50V,X7R"))
    )
    (comp (ref "C41")
      (value "0.1uF 0805")
      (footprint "CAP-CER_0603_L1.6W0.8H0.8_Wave")
      (description "0.1 (104) µF ±10% 50V Ceramic Capacitor X7R 0805 (2012 Metric)")
      (fields
        (field (name "MANUFACTURER PART NUMBER") "CC0805KRX7R9BB104")
        (field (name "TOLERANCE") "10%")
        (field (name "LIBRARY MADE BY") "MR. XUAN SIEU")
      )
      (libsource (lib "LIBRARY2026") (part "CAP_CER,SMD;0.1uF,10%,0805,50V,X7R"))
    )
    (comp (ref "C42")
      (value "0.1uF 0805")
      (footprint "CAP-CER_0603_L1.6W0.8H0.8_Wave")
      (description "0.1 (104) µF ±10% 50V Ceramic Capacitor X7R 0805 (2012 Metric)")
      (fields
        (field (name "MANUFACTURER PART NUMBER") "CC0805KRX7R9BB104")
        (field (name "TOLERANCE") "10%")
        (field (name "LIBRARY MADE BY") "MR. XUAN SIEU")
      )
      (libsource (lib "LIBRARY2026") (part "CAP_CER,SMD;0.1uF,10%,0805,50V,X7R"))
    )
    (comp (ref "C43")
      (value "0.1uF 0805")
      (footprint "CAP-CER_0603_L1.6W0.8H0.8_Wave")
      (description "0.1 (104) µF ±10% 50V Ceramic Capacitor X7R 0805 (2012 Metric)")
      (fields
        (field (name "MANUFACTURER PART NUMBER") "CC0805KRX7R9BB104")
        (field (name "TOLERANCE") "10%")
        (field (name "LIBRARY MADE BY") "MR. XUAN SIEU")
      )
      (libsource (lib "LIBRARY2026") (part "CAP_CER,SMD;0.1uF,10%,0805,50V,X7R"))
    )
    (comp (ref "C44")
      (value "0.1uF 0805")
      (footprint "CAP-CER_0603_L1.6W0.8H0.8_Wave")
      (description "0.1 (104) µF ±10% 50V Ceramic Capacitor X7R 0805 (2012 Metric)")
      (fields
        (field (name "MANUFACTURER PART NUMBER") "CC0805KRX7R9BB104")
        (field (name "TOLERANCE") "10%")
        (field (name "LIBRARY MADE BY") "MR. XUAN SIEU")
      )
      (libsource (lib "LIBRARY2026") (part "CAP_CER,SMD;0.1uF,10%,0805,50V,X7R"))
    )
    (comp (ref "C45")
      (value "0.1uF 0805")
      (footprint "CAP-CER_0603_L1.6W0.8H0.8_Wave")
      (description "0.1 (104) µF ±10% 50V Ceramic Capacitor X7R 0805 (2012 Metric)")
      (fields
        (field (name "MANUFACTURER PART NUMBER") "CC0805KRX7R9BB104")
        (field (name "TOLERANCE") "10%")
        (field (name "LIBRARY MADE BY") "MR. XUAN SIEU")
      )
      (libsource (lib "LIBRARY2026") (part "CAP_CER,SMD;0.1uF,10%,0805,50V,X7R"))
    )
    (comp (ref "C46")
      (value "0.1uF 0805")
      (footprint "CAP-CER_0603_L1.6W0.8H0.8_Wave")
      (description "0.1 (104) µF ±10% 50V Ceramic Capacitor X7R 0805 (2012 Metric)")
      (fields
        (field (name "MANUFACTURER PART NUMBER") "CC0805KRX7R9BB104")
        (field (name "TOLERANCE") "10%")
        (field (name "LIBRARY MADE BY") "MR. XUAN SIEU")
      )
      (libsource (lib "LIBRARY2026") (part "CAP_CER,SMD;0.1uF,10%,0805,50V,X7R"))
    )
    (comp (ref "C47")
      (value "0.1uF 0805")
      (footprint "CAP-CER_0603_L1.6W0.8H0.8_Wave")
      (description "0.1 (104) µF ±10% 50V Ceramic Capacitor X7R 0805 (2012 Metric)")
      (fields
        (field (name "MANUFACTURER PART NUMBER") "CC0805KRX7R9BB104")
        (field (name "TOLERANCE") "10%")
        (field (name "LIBRARY MADE BY") "MR. XUAN SIEU")
      )
      (libsource (lib "LIBRARY2026") (part "CAP_CER,SMD;0.1uF,10%,0805,50V,X7R"))
    )
    (comp (ref "C48")
      (value "0.1uF 0805")
      (footprint "CAP-CER_0603_L1.6W0.8H0.8_Wave")
      (description "0.1 (104) µF ±10% 50V Ceramic Capacitor X7R 0805 (2012 Metric)")
      (fields
        (field (name "MANUFACTURER PART NUMBER") "CC0805KRX7R9BB104")
        (field (name "TOLERANCE") "10%")
        (field (name "LIBRARY MADE BY") "MR. XUAN SIEU")
      )
      (libsource (lib "LIBRARY2026") (part "CAP_CER,SMD;0.1uF,10%,0805,50V,X7R"))
    )
    (comp (ref "D1")
      (value "SMF5.0A TVS Diode")
      (footprint "SOD-123")
      (description "9V (Typ) Clamp 1A (8/20¦Ìs) Ipp Tvs Diode Surface Mount SOD-923")
      (fields
        (field (name "MANUFACTURER PART NUMBER") "DF2S6.8FS,L3M")
        (field (name "LIBRARY MADE BY") "MR. XUAN SIEU")
      )
      (libsource (lib "SIM_A7680C") (part "DIODE,SMD;DF2S6,TVS,9V"))
    )
    (comp (ref "D2")
      (value "1N5822(SS34)-SM")
      (footprint "SMA-J_DO-214AC")
      (description "3.0A Schottky Barrier Rectifiers - Surface Mount")
      (libsource (lib "PCB_NODE_2") (part "1N5822(SS34)-SM"))
    )
    (comp (ref "D3")
      (value "Amber, 2V, 140°")
      (footprint "LED_0805_AMBER")
      (description "WL-SMCW Mono-color Chip LED Waterclear, SMT, size 0805, Amber, 2V, 140°")
      (fields
        (field (name "MANUFACTURER PART NUMBER") "150080AS75000")
        (field (name "MANUFACTURER") "Wurth Elektronik")
        (field (name "LIBRARY MADE BY") "MR. XUAN SIEU")
      )
      (libsource (lib "SIM_A7680C") (part "LED_SMD;0805,AMBER"))
    )
    (comp (ref "D4")
      (value "Amber, 2V, 140°")
      (footprint "LED_0805_AMBER")
      (description "WL-SMCW Mono-color Chip LED Waterclear, SMT, size 0805, Amber, 2V, 140°")
      (fields
        (field (name "MANUFACTURER PART NUMBER") "150080AS75000")
        (field (name "MANUFACTURER") "Wurth Elektronik")
        (field (name "LIBRARY MADE BY") "MR. XUAN SIEU")
      )
      (libsource (lib "SIM_A7680C") (part "LED_SMD;0805,AMBER"))
    )
    (comp (ref "D5")
      (value "1N5822(SS34)-SM")
      (footprint "SMA-J_DO-214AC")
      (description "3.0A Schottky Barrier Rectifiers - Surface Mount")
      (libsource (lib "PCB_NODE_2") (part "1N5822(SS34)-SM"))
    )
    (comp (ref "D6")
      (value "SMF5.0A")
      (footprint "SOD-123F/SOD-123FL")
      (description "9V (Typ) Clamp 1A (8/20¦Ìs) Ipp Tvs Diode Surface Mount SOD-923")
      (fields
        (field (name "MANUFACTURER PART NUMBER") "DF2S6.8FS,L3M")
        (field (name "LIBRARY MADE BY") "MR. XUAN SIEU")
      )
      (libsource (lib "SIM_A7680C") (part "DIODE,SMD;DF2S6,TVS,9V_1"))
    )
    (comp (ref "D7")
      (value "PWR SIM")
      (footprint "LED_0805_RED")
      (description "WL-SMCW Mono-color Chip LED Waterclear, SMT, size 0805, Red, 2V, 140°")
      (fields
        (field (name "MANUFACTURER PART NUMBER") "150080RS75000")
        (field (name "MANUFACTURER") "Wurth Elektronik")
        (field (name "LIBRARY MADE BY") "MR. XUAN SIEU")
      )
      (libsource (lib "PWR_3V3_5V_3V9") (part "LED_SMD;0805,RED"))
    )
    (comp (ref "D8")
      (value "Red, 2V, 140°")
      (footprint "LED_0805_RED")
      (description "WL-SMCW Mono-color Chip LED Waterclear, SMT, size 0805, Red, 2V, 140°")
      (fields
        (field (name "MANUFACTURER PART NUMBER") "150080RS75000")
        (field (name "MANUFACTURER") "Wurth Elektronik")
        (field (name "LIBRARY MADE BY") "MR. XUAN SIEU")
      )
      (libsource (lib "LIBRARY2026") (part "LED_SMD;0805,RED"))
    )
    (comp (ref "D9")
      (value "1N5227")
      (footprint "DIODE-SWITCHING_1N4148UR-1")
      (description "ZMM3V6 Diode Zener 0.5W 3.6V SOD-80")
      (fields
        (field (name "POWER") "200mA")
        (field (name "VOLTAGE") "75V")
        (field (name "LIBRARY MADE BY") "MR. XUAN SIEU")
      )
      (libsource (lib "LIBRARY2026") (part "DIODE_SMD;DIODE ZENER 3.6V"))
    )
    (comp (ref "DEBUG1")
      (value "jump 4P")
      (footprint "JUMP_M_1Sx4P_2.54MM")
      (description "Female, 4 C, Straight, .100\"CC; 3.20mm Tail, No Mounting; PBT, Phos. Bronze, 105 C")
      (fields
        (field (name "MANUFACTURER") "Sullins")
        (field (name "MANUFACTURER PART NUMBER") "PPPC041LFBN-RC")
      )
      (libsource (lib "LIBRARY2026") (part "JUMP_FEMALE;4P,2.54MM"))
    )
    (comp (ref "EC1")
      (value "100uF 16V")
      (footprint "CAP_ALU;SMD,D6.3H5.8")
      (description "100 µF 16 V Aluminum Electrolytic Capacitors Radial, Can - SMD 2000 Hrs @ 105°C")
      (fields
        (field (name "MANUFACTURER") "Wurth Electronics")
        (field (name "MANUFACTURER PART NUMBER") "865060343005")
        (field (name "LIBRARY MADE BY") "MR. XUAN SIEU")
      )
      (libsource (lib "SIM_A7680C") (part "CAP_ALU_SMD; 100UF 20% 16V 6.3x5.5MM"))
    )
    (comp (ref "EC2")
      (value "100uF 16V")
      (footprint "CAP_ALU;SMD,D6.3H5.8")
      (description "100 µF 16 V Aluminum Electrolytic Capacitors Radial, Can - SMD 2000 Hrs @ 105°C")
      (fields
        (field (name "MANUFACTURER") "Wurth Electronics")
        (field (name "MANUFACTURER PART NUMBER") "865060343005")
        (field (name "LIBRARY MADE BY") "MR. XUAN SIEU")
      )
      (libsource (lib "SIM_A7680C") (part "CAP_ALU_SMD; 100UF 20% 16V 6.3x5.5MM"))
    )
    (comp (ref "HOLE1")
      (value "HOLE_3M_1")
      (footprint "HOLE_M3_1")
      (libsource (lib "LIBRARY2026") (part "HOLE_3M_1"))
    )
    (comp (ref "HOLE2")
      (value "HOLE_3M_1")
      (footprint "HOLE_M3_1")
      (libsource (lib "LIBRARY2026") (part "HOLE_3M_1"))
    )
    (comp (ref "HOLE3")
      (value "HOLE_3M_1")
      (footprint "HOLE_M3_1")
      (libsource (lib "LIBRARY2026") (part "HOLE_3M_1"))
    )
    (comp (ref "HOLE4")
      (value "HOLE_3M_1")
      (footprint "HOLE_M3_1")
      (libsource (lib "LIBRARY2026") (part "HOLE_3M_1"))
    )
    (comp (ref "HOLE5")
      (value "HOLE_3M_1")
      (footprint "HOLE_M3_1")
      (libsource (lib "LIBRARY2026") (part "HOLE_3M_1"))
    )
    (comp (ref "HOLE6")
      (value "HOLE_3M_1")
      (footprint "HOLE_M3_1")
      (libsource (lib "LIBRARY2026") (part "HOLE_3M_1"))
    )
    (comp (ref "HOLE7")
      (value "HOLE_3M_1")
      (footprint "HOLE_M3_1")
      (libsource (lib "LIBRARY2026") (part "HOLE_3M_1"))
    )
    (comp (ref "HOLE8")
      (value "HOLE_3M_1")
      (footprint "HOLE_M3_1")
      (libsource (lib "LIBRARY2026") (part "HOLE_3M_1"))
    )
    (comp (ref "IC1")
      (value "AP62300")
      (footprint "SOT-23-6")
      (description "DC-DC Switching Synchronous Buck Regulator, Adjustable, 4.2V-18Vin, 0.8V-7V/3A out, TSOT-26-6")
      (fields
        (field (name "MANUFACTURER") "Diodes")
        (field (name "MANUFACTURER PART NUMBER") "AP62300TWU-7")
        (field (name "LIBRARY MADE BY") "MR. XUAN SIEU")
      )
      (libsource (lib "PWR_3V3_5V_3V9") (part "IC_SMD; IC REG LDO; SOT23-6; -40to85°C; AP62300TWU-7"))
    )
    (comp (ref "J1")
      (value "3P_2.00mm")
      (footprint "JST_B3B-PH-K-S(LF)(SN)")
      (description "Connector Header Through Hole 2 position 0.079 (2.00mm)")
      (fields (field (name "MF") "JST Sales America Inc.") (field (name "MP") "B3B-PH-K-S(LF)(SN)"))
      (libsource (lib "LIBRARY2026") (part "3P_2.00mm"))
    )
    (comp (ref "J2")
      (value "3P_2.00mm")
      (footprint "JST_B3B-PH-K-S(LF)(SN)")
      (description "Connector Header Through Hole 2 position 0.079 (2.00mm)")
      (fields (field (name "MF") "JST Sales America Inc.") (field (name "MP") "B3B-PH-K-S(LF)(SN)"))
      (libsource (lib "LIBRARY2026") (part "3P_2.00mm"))
    )
    (comp (ref "J3")
      (value "4P_2.00mm")
      (footprint "JST_B4B-PH-K-S(LF)(SN)")
      (description "Connector Header Through Hole 4 position 0.079 (2.00mm)")
      (fields (field (name "MF") "JST Sales") (field (name "MP") "B4B-PH-K-S (LF)(SN)"))
      (libsource (lib "") (part "4P_2.00mm_1"))
    )
    (comp (ref "J4")
      (value "3P_2.00mm")
      (footprint "JST_B3B-PH-K-S(LF)(SN)")
      (description "Connector Header Through Hole 2 position 0.079 (2.00mm)")
      (fields (field (name "MF") "JST Sales America Inc.") (field (name "MP") "B3B-PH-K-S(LF)(SN)"))
      (libsource (lib "LIBRARY2026") (part "3P_2.00mm"))
    )
    (comp (ref "J5")
      (value "4P_2.00mm")
      (footprint "JST_B4B-PH-K-S(LF)(SN)")
      (description "Connector Header Through Hole 4 position 0.079 (2.00mm)")
      (fields (field (name "MF") "JST Sales") (field (name "MP") "B4B-PH-K-S (LF)(SN)"))
      (libsource (lib "LIBRARY2026") (part "4P_2.00mm"))
    )
    (comp (ref "J6")
      (value "3P_2.00mm")
      (footprint "JST_B3B-PH-K-S(LF)(SN)")
      (description "Connector Header Through Hole 2 position 0.079 (2.00mm)")
      (fields (field (name "MF") "JST Sales America Inc.") (field (name "MP") "B3B-PH-K-S(LF)(SN)"))
      (libsource (lib "") (part "3P_2.00mm_1"))
    )
    (comp (ref "J7")
      (value "3P_2.00mm")
      (footprint "JST_B3B-PH-K-S(LF)(SN)")
      (description "Connector Header Through Hole 2 position 0.079 (2.00mm)")
      (fields (field (name "MF") "JST Sales America Inc.") (field (name "MP") "B3B-PH-K-S(LF)(SN)"))
      (libsource (lib "") (part "3P_2.00mm_1"))
    )
    (comp (ref "J8")
      (value "4P_2.00mm")
      (footprint "JST_B4B-PH-K-S(LF)(SN)")
      (description "Connector Header Through Hole 4 position 0.079 (2.00mm)")
      (fields (field (name "MF") "JST Sales") (field (name "MP") "B4B-PH-K-S (LF)(SN)"))
      (libsource (lib "LIBRARY2026") (part "4P_2.00mm"))
    )
    (comp (ref "J9")
      (value "Type C")
      (footprint "USB_C_6P_2.00")
      (description "USB Type C - Connector, Top-mount, SMT, 6pos ¦ Molex Incorporated 217175-0001")
      (fields
        (field (name "MANUFACTURER PART NUMBER") "217175-0001")
        (field (name "LIBRARY MADE BY") "MR. XUAN SIEU")
      )
      (libsource (lib "ALTIUM_DESIGN") (part "CONN_SMD,TYPE-C,6P"))
    )
    (comp (ref "J10")
      (value "4P_2.00mm")
      (footprint "JST_B4B-PH-K-S(LF)(SN)")
      (description "Connector Header Through Hole 4 position 0.079 (2.00mm)")
      (fields (field (name "MF") "JST Sales") (field (name "MP") "B4B-PH-K-S (LF)(SN)"))
      (libsource (lib "") (part "4P_2.00mm_1"))
    )
    (comp (ref "J11")
      (value "CON_TH_8P_2.0MM")
      (footprint "JST_B8B-PH-K-S")
      (description "2.0 mm pitch/Disconnectable Crimp style connectors")
      (fields (field (name "MF") "JST") (field (name "MP") "B8B-PH-K-S"))
      (libsource (lib "LIBRARY2026") (part "CON_TH_8P_2.0MM"))
    )
    (comp (ref "J12")
      (value "4P_2.00mm")
      (footprint "JST_B4B-PH-K-S(LF)(SN)")
      (description "Connector Header Through Hole 4 position 0.079 (2.00mm)")
      (fields (field (name "MF") "JST Sales") (field (name "MP") "B4B-PH-K-S (LF)(SN)"))
      (libsource (lib "") (part "4P_2.00mm_1"))
    )
    (comp (ref "L1")
      (value "BLM21PG300SN1D")
      (footprint "FB_0805_L2W1.2H0.9_HC")
      (description "FERRITE BEAD")
      (fields (field (name "PUBLISHER") "Altium Limited"))
      (libsource (lib "SIM_A7680C") (part "Ferrite Bead"))
    )
    (comp (ref "L2")
      (value "22uH")
      (footprint "L-WIRE-CDRH74R-SM")
      (description "Wirewound Inductor - Surface Mount")
      (libsource (lib "PCB_NODE_2") (part "L-WIRE-SM"))
    )
    (comp (ref "L3")
      (value "22uH")
      (footprint "L-WIRE-CDRH74R-SM")
      (description "Wirewound Inductor - Surface Mount")
      (libsource (lib "PCB_NODE_2") (part "L-WIRE-SM"))
    )
    (comp (ref "L4")
      (value "3.3uH 3.4A")
      (footprint "IND_SMD 6x6x2.8MM")
      (description "Inductor Power Shielded/Molded Wirewound 3.3uH 20% 100KHz Ferrite 3.4A 0.028Ohm DCR 2424 T/R")
      (fields
        (field (name "MANUFACTURER") "Abracon")
        (field (name "MANUFACTURER PART NUMBER") "ASPI-0628-3R3M-T1")
        (field (name "LIBRARY MADE BY") "MR. XUAN SIEU")
      )
      (libsource (lib "PWR_3V3_5V_3V9") (part "IND_SMD; FIXED IND 3.3UH 3.4A 28 MOHM 6x6x2.8MM"))
    )
    (comp (ref "LS1")
      (value "BUZZ_9X5.5MM")
      (footprint "CUI_CST-931AP")
      (description "9 mm, 3 V, 85 dB, Through Hole, Magnetic Audio Transducer Buzzer")
      (fields (field (name "MF") "Same Sky") (field (name "MP") "CST-931AP"))
      (libsource (lib "LIBRARY2026") (part "BUZZ_9X5.5MM"))
    )
    (comp (ref "M1")
      (value "SIM A7680C")
      (footprint "IC_SIM_A7682S/A7680C - duplicate")
      (description "Cellular module; LTE Cat1 bis; GNSS (option)")
      (fields
        (field (name "MP") "SIM868")
        (field (name "MF") "MikroElektronika")
        (field (name "LIBRARY MADE BY") "MR. XUAN SIEU")
      )
      (libsource (lib "SIM_A7680C") (part "MODULE_SMD; MODULE SIM 4G, A7680C_CHIP"))
    )
    (comp (ref "PWR_DISPLAY1")
      (value "LED-CHIP-SM")
      (footprint "LED-CHIP-0805-RD-SM")
      (description "Chip LED - Surface Mount")
      (libsource (lib "PCB_NODE_2") (part "LED-CHIP-SM"))
    )
    (comp (ref "PWR_STM1")
      (value "LED-CHIP-SM")
      (footprint "LED-CHIP-0805-RD-SM")
      (description "Chip LED - Surface Mount")
      (libsource (lib "PCB_NODE_2") (part "LED-CHIP-SM"))
    )
    (comp (ref "Q1")
      (value "NPN 25V 1.5A")
      (footprint "MOS-FET; SOT23")
      (description "Trans Gp Bjt NPN 25V 1.5A 300MW 3-PIN SOT-23 T/r")
      (fields
        (field (name "MANUFACTURER PART NUMBER") "SS8050-G")
        (field (name "LIBRARY MADE BY") "MR. XUAN SIEU")
      )
      (libsource (lib "SIM_A7680C") (part "TRANS-BJT_SMD; NPN, 25V, 1.5A, SOT-23, SS8050-G"))
    )
    (comp (ref "Q2")
      (value "NPN 25V 1.5A")
      (footprint "MOS-FET; SOT23")
      (description "Trans Gp Bjt NPN 25V 1.5A 300MW 3-PIN SOT-23 T/r")
      (fields
        (field (name "MANUFACTURER PART NUMBER") "SS8050-G")
        (field (name "LIBRARY MADE BY") "MR. XUAN SIEU")
      )
      (libsource (lib "") (part "TRANS-BJT_SMD; NPN, 25V, 1.5A, SOT-23, SS8050-G_2"))
    )
    (comp (ref "Q3")
      (value "NPN 25V 1.5A")
      (footprint "MOS-FET; SOT23")
      (description "Trans Gp Bjt NPN 25V 1.5A 300MW 3-PIN SOT-23 T/r")
      (fields
        (field (name "MANUFACTURER PART NUMBER") "SS8050-G")
        (field (name "LIBRARY MADE BY") "MR. XUAN SIEU")
      )
      (libsource (lib "SIM_A7680C") (part "TRANS-BJT_SMD; NPN 25V 1.5A SOT-23-3; SS8050-G"))
    )
    (comp (ref "Q4")
      (value "NPN 25V 1.5A")
      (footprint "MOS-FET; SOT23")
      (description "Trans Gp Bjt NPN 25V 1.5A 300MW 3-PIN SOT-23 T/r")
      (fields
        (field (name "MANUFACTURER PART NUMBER") "SS8050-G")
        (field (name "LIBRARY MADE BY") "MR. XUAN SIEU")
      )
      (libsource (lib "SIM_A7680C") (part "TRANS-BJT_SMD; NPN 25V 1.5A SOT-23-3; SS8050-G"))
    )
    (comp (ref "Q5")
      (value "NPN 25V 1.5A")
      (footprint "MOS-FET; SOT23")
      (description "Trans Gp Bjt NPN 25V 1.5A 300MW 3-PIN SOT-23 T/r")
      (fields
        (field (name "MANUFACTURER PART NUMBER") "SS8050-G")
        (field (name "LIBRARY MADE BY") "MR. XUAN SIEU")
      )
      (libsource (lib "") (part "TRANS-BJT_SMD; NPN, 25V, 1.5A, SOT-23, SS8050-G_1"))
    )
    (comp (ref "Q6")
      (value "NPN 25V 1.5A")
      (footprint "MOS-FET; SOT23")
      (description "Trans Gp Bjt NPN 25V 1.5A 300MW 3-PIN SOT-23 T/r")
      (fields
        (field (name "MANUFACTURER PART NUMBER") "SS8050-G")
        (field (name "LIBRARY MADE BY") "MR. XUAN SIEU")
      )
      (libsource (lib "LIBRARY2026") (part "TRANS-BJT_SMD; NPN, 25V, 1.5A, SOT-23, SS8050-G"))
    )
    (comp (ref "R1")
      (value "4k7 1%")
      (footprint "RESISTOR_0805_Wave")
      (description "Res Thick Film 0805 4.7K Ohm 1% 1/8W ±100ppm/°C Molded SMD Paper T/R")
      (fields
        (field (name "MANUFACTURER PART NUMBER") "CRCW08054K70FKEAC")
        (field (name "LIBRARY MADE BY") "MR. XUAN SIEU")
      )
      (libsource (lib "SIM_A7680C") (part "RES_SMD; 4.7K, 1%, 0805, 1/8W"))
    )
    (comp (ref "R2")
      (value "4k7 1%")
      (footprint "RESISTOR_0805_Wave")
      (description "Res Thick Film 0805 4.7K Ohm 1% 1/8W ±100ppm/°C Molded SMD Paper T/R")
      (fields
        (field (name "MANUFACTURER PART NUMBER") "CRCW08054K70FKEAC")
        (field (name "LIBRARY MADE BY") "MR. XUAN SIEU")
      )
      (libsource (lib "SIM_A7680C") (part "RES_SMD; 4.7K, 1%, 0805, 1/8W"))
    )
    (comp (ref "R3")
      (value "100kΩ ±1% 125mW")
      (footprint "R-CHIP-0805-SM")
      (description "10kΩ 100mW 75V ±1% ±100ppm/℃ Thick Film Resistor 0603 Chip Resistor - Surface Mount ROHS")
      (fields (field (name "MANUFACTURER") "YAGEO") (field (name "USER") "1"))
      (libsource (lib "PCB_NODE_2") (part "R-SM"))
    )
    (comp (ref "R4")
      (value "0Ω ±1% 125mW")
      (footprint "R-CHIP-0805-SM")
      (description "10kΩ 100mW 75V ±1% ±100ppm/℃ Thick Film Resistor 0603 Chip Resistor - Surface Mount ROHS")
      (fields (field (name "MANUFACTURER") "YAGEO") (field (name "USER") "1"))
      (libsource (lib "PCB_NODE_2") (part "R-SM_4"))
    )
    (comp (ref "R5")
      (value "4k7 1%")
      (footprint "RESISTOR_0805_Wave")
      (description "Res Thick Film 0805 4.7K Ohm 1% 1/8W ±100ppm/°C Molded SMD Paper T/R")
      (fields
        (field (name "MANUFACTURER PART NUMBER") "CRCW08054K70FKEAC")
        (field (name "LIBRARY MADE BY") "MR. XUAN SIEU")
      )
      (libsource (lib "SIM_A7680C") (part "RES_SMD; 4.7K, 1%, 0805, 1/8W"))
    )
    (comp (ref "R6")
      (value "68kΩ ±1% 125mW")
      (footprint "R-CHIP-0805-SM")
      (description "10kΩ 100mW 75V ±1% ±100ppm/℃ Thick Film Resistor 0603 Chip Resistor - Surface Mount ROHS")
      (fields (field (name "MANUFACTURER") "YAGEO") (field (name "USER") "1"))
      (libsource (lib "PCB_NODE_2") (part "R-SM_1"))
    )
    (comp (ref "R7")
      (value "4k7 1%")
      (footprint "RESISTOR_0805_Wave")
      (description "Res Thick Film 0805 4.7K Ohm 1% 1/8W ±100ppm/°C Molded SMD Paper T/R")
      (fields
        (field (name "MANUFACTURER PART NUMBER") "CRCW08054K70FKEAC")
        (field (name "LIBRARY MADE BY") "MR. XUAN SIEU")
      )
      (libsource (lib "SIM_A7680C") (part "RES_SMD; 4.7K, 1%, 0805, 1/8W"))
    )
    (comp (ref "R8")
      (value "47K 1%")
      (footprint "RESISTOR_0805_Wave")
      (description "125Mw Thick Film Resistors 100Ppm/ 1% 47K 0805 Chip Resistor Surface Mount Rohs")
      (fields
        (field (name "MANUFACTURER") "Yageo")
        (field (name "MANUFACTURER PART NUMBER") "RC0805FR-0747KL")
        (field (name "LIBRARY MADE BY") "MR. XUAN SIEU")
      )
      (libsource (lib "SIM_A7680C") (part "RES_SMD; 47K, 1%, 0805, 1/8W"))
    )
    (comp (ref "R9")
      (value "1kΩ ±1% 125mW")
      (footprint "R-CHIP-0805-SM")
      (description "10kΩ 100mW 75V ±1% ±100ppm/℃ Thick Film Resistor 0603 Chip Resistor - Surface Mount ROHS")
      (fields (field (name "MANUFACTURER") "YAGEO") (field (name "USER") "1"))
      (libsource (lib "PCB_NODE_2") (part "R-SM_5"))
    )
    (comp (ref "R10")
      (value "20kΩ ±1% 125mW")
      (footprint "R-CHIP-0805-SM")
      (description "10kΩ 100mW 75V ±1% ±100ppm/℃ Thick Film Resistor 0603 Chip Resistor - Surface Mount ROHS")
      (fields (field (name "MANUFACTURER") "YAGEO") (field (name "USER") "1"))
      (libsource (lib "PCB_NODE_2") (part "R-SM_2"))
    )
    (comp (ref "R11")
      (value "10K 1%")
      (footprint "RESISTOR_0805_Wave")
      (description "SMD Chip Resistor, 10 kOhm, ± 1%, 125 mW, 0805 [2012 Metric], Thick Film, General Purpose")
      (fields
        (field (name "MANUFACTURER PART NUMBER") "RMCF0805FT10K0")
        (field (name "LIBRARY MADE BY") "MR. XUAN SIEU")
      )
      (libsource (lib "LIBRARY2026") (part "RES_SMD; 10K, 1%, 0805, 1/8W"))
    )
    (comp (ref "R12")
      (value "22R 1%")
      (footprint "RESISTOR_0805_Wave")
      (description "SMD Chip Resistor, 22 Ohm, ± 1%, 125 mW, 0805 [2012 Metric], Thick Film, General Purpose")
      (fields
        (field (name "MANUFACTURER PART NUMBER") "RC0805FR-0722RL")
        (field (name "LIBRARY MADE BY") "MR. XUAN SIEU")
      )
      (libsource (lib "SIM_A7680C") (part "RES_SMD; 22R, 1%, 0805, 1/8W"))
    )
    (comp (ref "R13")
      (value "22R 1%")
      (footprint "RESISTOR_0805_Wave")
      (description "SMD Chip Resistor, 22 Ohm, ± 1%, 125 mW, 0805 [2012 Metric], Thick Film, General Purpose")
      (fields
        (field (name "MANUFACTURER PART NUMBER") "RC0805FR-0722RL")
        (field (name "LIBRARY MADE BY") "MR. XUAN SIEU")
      )
      (libsource (lib "SIM_A7680C") (part "RES_SMD; 22R, 1%, 0805, 1/8W"))
    )
    (comp (ref "R14")
      (value "22R 1%")
      (footprint "RESISTOR_0805_Wave")
      (description "SMD Chip Resistor, 22 Ohm, ± 1%, 125 mW, 0805 [2012 Metric], Thick Film, General Purpose")
      (fields
        (field (name "MANUFACTURER PART NUMBER") "RC0805FR-0722RL")
        (field (name "LIBRARY MADE BY") "MR. XUAN SIEU")
      )
      (libsource (lib "SIM_A7680C") (part "RES_SMD; 22R, 1%, 0805, 1/8W"))
    )
    (comp (ref "R15")
      (value "2K2")
      (footprint "RESISTOR_0805_Wave")
      (description "Res Thick Film 0805 2.2K Ohm 1% 0.125W(1/8W) ±100ppm/C Pad SMD T/R")
      (fields
        (field (name "MANUFACTURER PART NUMBER") "CRG0805F2K2")
        (field (name "TOLERANCE") "1%")
        (field (name "LIBRARY MADE BY") "MR. XUAN SIEU")
      )
      (libsource (lib "SIM_A7680C") (part "RES_SMD; 2.2K, 1%, 0805, 1/8W"))
    )
    (comp (ref "R16")
      (value "22R 1%")
      (footprint "RESISTOR_0805_Wave")
      (description "SMD Chip Resistor, 22 Ohm, ± 1%, 125 mW, 0805 [2012 Metric], Thick Film, General Purpose")
      (fields
        (field (name "MANUFACTURER PART NUMBER") "RC0805FR-0722RL")
        (field (name "LIBRARY MADE BY") "MR. XUAN SIEU")
      )
      (libsource (lib "SIM_A7680C") (part "RES_SMD; 22R, 1%, 0805, 1/8W"))
    )
    (comp (ref "R17")
      (value "2K2")
      (footprint "RESISTOR_0805_Wave")
      (description "Res Thick Film 0805 2.2K Ohm 1% 0.125W(1/8W) ±100ppm/C Pad SMD T/R")
      (fields
        (field (name "MANUFACTURER PART NUMBER") "CRG0805F2K2")
        (field (name "TOLERANCE") "1%")
        (field (name "LIBRARY MADE BY") "MR. XUAN SIEU")
      )
      (libsource (lib "SIM_A7680C") (part "RES_SMD; 2.2K, 1%, 0805, 1/8W"))
    )
    (comp (ref "R18")
      (value "22R 1%")
      (footprint "RESISTOR_0805_Wave")
      (description "SMD Chip Resistor, 22 Ohm, ± 1%, 125 mW, 0805 [2012 Metric], Thick Film, General Purpose")
      (fields
        (field (name "MANUFACTURER PART NUMBER") "RC0805FR-0722RL")
        (field (name "LIBRARY MADE BY") "MR. XUAN SIEU")
      )
      (libsource (lib "SIM_A7680C") (part "RES_SMD; 22R, 1%, 0805, 1/8W"))
    )
    (comp (ref "R19")
      (value "4k7 1%")
      (footprint "RESISTOR_0805_Wave")
      (description "Res Thick Film 0805 4.7K Ohm 1% 1/8W ±100ppm/°C Molded SMD Paper T/R")
      (fields
        (field (name "MANUFACTURER PART NUMBER") "CRCW08054K70FKEAC")
        (field (name "LIBRARY MADE BY") "MR. XUAN SIEU")
      )
      (libsource (lib "SIM_A7680C") (part "RES_SMD; 4.7K, 1%, 0805, 1/8W"))
    )
    (comp (ref "R20")
      (value "100kΩ ±1% 125mW")
      (footprint "R-CHIP-0805-SM")
      (description "10kΩ 100mW 75V ±1% ±100ppm/℃ Thick Film Resistor 0603 Chip Resistor - Surface Mount ROHS")
      (fields (field (name "MANUFACTURER") "YAGEO") (field (name "USER") "1"))
      (libsource (lib "PCB_NODE_2") (part "R-SM"))
    )
    (comp (ref "R21")
      (value "0Ω ±1% 125mW")
      (footprint "R-CHIP-0805-SM")
      (description "10kΩ 100mW 75V ±1% ±100ppm/℃ Thick Film Resistor 0603 Chip Resistor - Surface Mount ROHS")
      (fields (field (name "MANUFACTURER") "YAGEO") (field (name "USER") "1"))
      (libsource (lib "PCB_NODE_2") (part "R-SM_4"))
    )
    (comp (ref "R22")
      (value "68kΩ ±1% 125mW")
      (footprint "R-CHIP-0805-SM")
      (description "10kΩ 100mW 75V ±1% ±100ppm/℃ Thick Film Resistor 0603 Chip Resistor - Surface Mount ROHS")
      (fields (field (name "MANUFACTURER") "YAGEO") (field (name "USER") "1"))
      (libsource (lib "PCB_NODE_2") (part "R-SM_1"))
    )
    (comp (ref "R23")
      (value "4k7 1%")
      (footprint "RESISTOR_0805_Wave")
      (description "Res Thick Film 0805 4.7K Ohm 1% 1/8W ±100ppm/°C Molded SMD Paper T/R")
      (fields
        (field (name "MANUFACTURER PART NUMBER") "CRCW08054K70FKEAC")
        (field (name "LIBRARY MADE BY") "MR. XUAN SIEU")
      )
      (libsource (lib "SIM_A7680C") (part "RES_SMD; 4.7K, 1%, 0805, 1/8W"))
    )
    (comp (ref "R24")
      (value "1kΩ ±1% 125mW")
      (footprint "R-CHIP-0805-SM")
      (description "10kΩ 100mW 75V ±1% ±100ppm/℃ Thick Film Resistor 0603 Chip Resistor - Surface Mount ROHS")
      (fields (field (name "MANUFACTURER") "YAGEO") (field (name "USER") "1"))
      (libsource (lib "PCB_NODE_2") (part "R-SM_5"))
    )
    (comp (ref "R25")
      (value "47K 1%")
      (footprint "RESISTOR_0805_Wave")
      (description "125Mw Thick Film Resistors 100Ppm/ 1% 47K 0805 Chip Resistor Surface Mount Rohs")
      (fields
        (field (name "MANUFACTURER") "Yageo")
        (field (name "MANUFACTURER PART NUMBER") "RC0805FR-0747KL")
        (field (name "LIBRARY MADE BY") "MR. XUAN SIEU")
      )
      (libsource (lib "LIBRARY2026") (part "RES_SMD; 47K, 1%, 0805, 1/8W_1"))
    )
    (comp (ref "R26")
      (value "10K 1%")
      (footprint "RESISTOR_0805_Wave")
      (description "SMD Chip Resistor, 10 kOhm, ± 1%, 125 mW, 0805 [2012 Metric], Thick Film, General Purpose")
      (fields
        (field (name "MANUFACTURER PART NUMBER") "RMCF0805FT10K0")
        (field (name "LIBRARY MADE BY") "MR. XUAN SIEU")
      )
      (libsource (lib "LIBRARY2026") (part "RES_SMD; 10K, 1%, 0805, 1/8W"))
    )
    (comp (ref "R27")
      (value "47K 1%")
      (footprint "RESISTOR_0805_Wave")
      (description "125Mw Thick Film Resistors 100Ppm/ 1% 47K 0805 Chip Resistor Surface Mount Rohs")
      (fields
        (field (name "MANUFACTURER") "Yageo")
        (field (name "MANUFACTURER PART NUMBER") "RC0805FR-0747KL")
        (field (name "LIBRARY MADE BY") "MR. XUAN SIEU")
      )
      (libsource (lib "LIBRARY2026") (part "RES_SMD; 47K, 1%, 0805, 1/8W_1"))
    )
    (comp (ref "R28")
      (value "20kΩ ±1% 125mW")
      (footprint "R-CHIP-0805-SM")
      (description "10kΩ 100mW 75V ±1% ±100ppm/℃ Thick Film Resistor 0603 Chip Resistor - Surface Mount ROHS")
      (fields (field (name "MANUFACTURER") "YAGEO") (field (name "USER") "1"))
      (libsource (lib "PCB_NODE_2") (part "R-SM_2"))
    )
    (comp (ref "R29")
      (value "4k7 1%")
      (footprint "RESISTOR_0805_Wave")
      (description "Res Thick Film 0805 4.7K Ohm 1% 1/8W ±100ppm/°C Molded SMD Paper T/R")
      (fields
        (field (name "MANUFACTURER PART NUMBER") "CRCW08054K70FKEAC")
        (field (name "LIBRARY MADE BY") "MR. XUAN SIEU")
      )
      (libsource (lib "SIM_A7680C") (part "RES_SMD; 4.7K, 1%, 0805, 1/8W"))
    )
    (comp (ref "R30")
      (value "47K 1%")
      (footprint "RESISTOR_0805_Wave")
      (description "125Mw Thick Film Resistors 100Ppm/ 1% 47K 0805 Chip Resistor Surface Mount Rohs")
      (fields
        (field (name "MANUFACTURER") "Yageo")
        (field (name "MANUFACTURER PART NUMBER") "RC0805FR-0747KL")
        (field (name "LIBRARY MADE BY") "MR. XUAN SIEU")
      )
      (libsource (lib "LIBRARY2026") (part "RES_SMD; 47K, 1%, 0805, 1/8W_1"))
    )
    (comp (ref "R31")
      (value "100K 1%")
      (footprint "RESISTOR_0805_Wave")
      (description "SMD Chip Resistor, 100 kOhm, ï¿½ 1%, 125 mW, 0805 [2012 Metric], Thick Film, General Purpose")
      (fields
        (field (name "MANUFACTURER PART NUMBER") "RC0805FR-07100KL")
        (field (name "TOLERANCE") "1%")
        (field (name "LIBRARY MADE BY") "MR. XUAN SIEU")
      )
      (libsource (lib "PWR_3V3_5V_3V9") (part "RES_SMD; 100K, 1%, 0805, 1/8W"))
    )
    (comp (ref "R32")
      (value "10K 1%")
      (footprint "RESISTOR_0805_Wave")
      (description "SMD Chip Resistor, 10 kOhm, ± 1%, 125 mW, 0805 [2012 Metric], Thick Film, General Purpose")
      (fields
        (field (name "MANUFACTURER PART NUMBER") "RMCF0805FT10K0")
        (field (name "LIBRARY MADE BY") "MR. XUAN SIEU")
      )
      (libsource (lib "LIBRARY2026") (part "RES_SMD; 10K, 1%, 0805, 1/8W"))
    )
    (comp (ref "R33")
      (value "330R 1%")
      (footprint "RESISTOR_0805_Wave")
      (description "Res Thick Film 0805 330 Ohm 1% 0.125W ±100ppm/°C Molded SMD Paper T/R")
      (fields
        (field (name "MANUFACTURER") "Stackpole Electronics")
        (field (name "MANUFACTURER PART NUMBER") "RMCF0805FT330R")
        (field (name "LIBRARY MADE BY") "MR. XUAN SIEU")
      )
      (libsource (lib "PWR_3V3_5V_3V9") (part "RES_SMD; 330R, 1%, 0805, 1/8W"))
    )
    (comp (ref "R34")
      (value "39K 1%")
      (footprint "RESISTOR_0805_Wave")
      (description "125Mw Thick Film Resistors 100Ppm/ 1% 47K 0805 Chip Resistor Surface Mount Rohs")
      (fields
        (field (name "MANUFACTURER") "Yageo")
        (field (name "MANUFACTURER PART NUMBER") "RC0805FR-0747KL")
        (field (name "LIBRARY MADE BY") "MR. XUAN SIEU")
      )
      (libsource (lib "PWR_3V3_5V_3V9") (part "RES_SMD; 47K, 1%, 0805, 1/8W"))
    )
    (comp (ref "R35")
      (value "10K 1%")
      (footprint "RESISTOR_0805_Wave")
      (description "SMD Chip Resistor, 10 kOhm, ± 1%, 125 mW, 0805 [2012 Metric], Thick Film, General Purpose")
      (fields
        (field (name "MANUFACTURER PART NUMBER") "RMCF0805FT10K0")
        (field (name "LIBRARY MADE BY") "MR. XUAN SIEU")
      )
      (libsource (lib "PWR_3V3_5V_3V9") (part "RES_SMD; 10K, 1%, 0805, 1/8W"))
    )
    (comp (ref "R36")
      (value "10kΩ ±1% 125mW")
      (footprint "R-CHIP-0805-SM")
      (description "10kΩ 100mW 75V ±1% ±100ppm/℃ Thick Film Resistor 0603 Chip Resistor - Surface Mount ROHS")
      (fields (field (name "MANUFACTURER") "YAGEO") (field (name "USER") "1"))
      (libsource (lib "PCB_NODE_2") (part "R-SM_3"))
    )
    (comp (ref "R37")
      (value "10K 1%")
      (footprint "RESISTOR_0805_Wave")
      (description "SMD Chip Resistor, 10 kOhm, ± 1%, 125 mW, 0805 [2012 Metric], Thick Film, General Purpose")
      (fields
        (field (name "MANUFACTURER PART NUMBER") "RMCF0805FT10K0")
        (field (name "LIBRARY MADE BY") "MR. XUAN SIEU")
      )
      (libsource (lib "LIBRARY2026") (part "RES_SMD; 10K, 1%, 0805, 1/8W"))
    )
    (comp (ref "R38")
      (value "10K 1%")
      (footprint "RESISTOR_0805_Wave")
      (description "SMD Chip Resistor, 10 kOhm, ± 1%, 125 mW, 0805 [2012 Metric], Thick Film, General Purpose")
      (fields
        (field (name "MANUFACTURER PART NUMBER") "RMCF0805FT10K0")
        (field (name "LIBRARY MADE BY") "MR. XUAN SIEU")
      )
      (libsource (lib "LIBRARY2026") (part "RES_SMD; 10K, 1%, 0805, 1/8W"))
    )
    (comp (ref "R39")
      (value "10K 1%")
      (footprint "RESISTOR_0805_Wave")
      (description "SMD Chip Resistor, 10 kOhm, ± 1%, 125 mW, 0805 [2012 Metric], Thick Film, General Purpose")
      (fields
        (field (name "MANUFACTURER PART NUMBER") "RMCF0805FT10K0")
        (field (name "LIBRARY MADE BY") "MR. XUAN SIEU")
      )
      (libsource (lib "LIBRARY2026") (part "RES_SMD; 10K, 1%, 0805, 1/8W"))
    )
    (comp (ref "R40")
      (value "1K 0805")
      (footprint "RESISTOR_0805_Wave")
      (description "1K\r\nSIMPLE SWITCHER® 4.5V to 40V, 3A Low Component Count Step-Down Regulator 5-DDPAK/TO-263")
      (fields
        (field (name "MANUFACTURER PART NUMBER") "RNCP0805FTD1K00")
        (field (name "LIBRARY MADE BY") "MR. XUAN SIEU")
      )
      (libsource (lib "LIBRARY2026") (part "RES_SMD; 1K, 1%, 0805, 1/8W"))
    )
    (comp (ref "R41")
      (value "100R 1%")
      (footprint "RESISTOR_0805_Reflow")
      (description "100 Ohms ±1% 0.125W, 1/8W Chip Resistor 0805 (2012 Metric) Moisture Resistant Thick Film")
      (fields
        (field (name "MANUFACTURER") "Yageo")
        (field (name "MANUFACTURER PART NUMBER") "RC0805FR-07470RL")
        (field (name "LIBRARY MADE BY") "MR. XUAN SIEU")
      )
      (libsource (lib "LIBRARY2026") (part "RES_SMD; 100r, 1%, 0805, 1/8W_1"))
    )
    (comp (ref "R42")
      (value "1K 0805")
      (footprint "RESISTOR_0805_Wave")
      (description "1K\r\nSIMPLE SWITCHER® 4.5V to 40V, 3A Low Component Count Step-Down Regulator 5-DDPAK/TO-263")
      (fields
        (field (name "MANUFACTURER PART NUMBER") "RNCP0805FTD1K00")
        (field (name "LIBRARY MADE BY") "MR. XUAN SIEU")
      )
      (libsource (lib "LIBRARY2026") (part "RES_SMD; 1K, 1%, 0805, 1/8W"))
    )
    (comp (ref "R43")
      (value "10K 1%")
      (footprint "RESISTOR_0805_Wave")
      (description "SMD Chip Resistor, 10 kOhm, ± 1%, 125 mW, 0805 [2012 Metric], Thick Film, General Purpose")
      (fields
        (field (name "MANUFACTURER PART NUMBER") "RMCF0805FT10K0")
        (field (name "LIBRARY MADE BY") "MR. XUAN SIEU")
      )
      (libsource (lib "LIBRARY2026") (part "RES_SMD; 10K, 1%, 0805, 1/8W"))
    )
    (comp (ref "R44")
      (value "100K 1%")
      (footprint "RESISTOR_0805_Wave")
      (description "SMD Chip Resistor, 100 kOhm, ï¿½ 1%, 125 mW, 0805 [2012 Metric], Thick Film, General Purpose")
      (fields
        (field (name "MANUFACTURER PART NUMBER") "RC0805FR-07100KL")
        (field (name "TOLERANCE") "1%")
        (field (name "LIBRARY MADE BY") "MR. XUAN SIEU")
      )
      (libsource (lib "LIBRARY2026") (part "RES_SMD; 100K, 1%, 0805, 1/8W"))
    )
    (comp (ref "R45")
      (value "100R 1%")
      (footprint "RESISTOR_0805_Reflow")
      (description "100 Ohms ±1% 0.125W, 1/8W Chip Resistor 0805 (2012 Metric) Moisture Resistant Thick Film")
      (fields
        (field (name "MANUFACTURER") "Yageo")
        (field (name "MANUFACTURER PART NUMBER") "RC0805FR-07470RL")
        (field (name "LIBRARY MADE BY") "MR. XUAN SIEU")
      )
      (libsource (lib "LIBRARY2026") (part "RES_SMD; 100r, 1%, 0805, 1/8W_1"))
    )
    (comp (ref "R46")
      (value "47K 1%")
      (footprint "RESISTOR_0805_Wave")
      (description "125Mw Thick Film Resistors 100Ppm/ 1% 47K 0805 Chip Resistor Surface Mount Rohs")
      (fields
        (field (name "MANUFACTURER") "Yageo")
        (field (name "MANUFACTURER PART NUMBER") "RC0805FR-0747KL")
        (field (name "LIBRARY MADE BY") "MR. XUAN SIEU")
      )
      (libsource (lib "LIBRARY2026") (part "RES_SMD; 47K, 1%, 0805, 1/8W_1"))
    )
    (comp (ref "RC1")
      (value "0R 0805")
      (footprint "RESISTOR_0603_Wave")
      (fields
        (field (name "MANUFACTURER PART NUMBER") "CR0805AJ/-000EAS")
        (field (name "TOLERANCE") "5%")
        (field (name "LIBRARY MADE BY") "MR. XUAN SIEU")
      )
      (libsource (lib "LIBRARY2026") (part "RES_SMD; 0R 5% 1/8W 0805"))
    )
    (comp (ref "SW1")
      (value "4.5x4.5")
      (footprint "SWITCH_SMD_4P_4.5x4.5x3.8MM - duplicate")
      (description "Switch Tactile N.O. SPST Round Button Gull Wing 0.05A 12VDC 100000Cycles 1.57N SMD T/R")
      (fields
        (field (name "MANUFACTURER PART NUMBER") "PTS645SM43SMTR92LFS")
        (field (name "LIBRARY MADE BY") "MR. XUAN SIEU")
      )
      (libsource (lib "LIBRARY2026") (part "SWITCH-SMD;4P,TACTILE,4.5x4.5mm"))
    )
    (comp (ref "SW2")
      (value "4.5x4.5")
      (footprint "SWITCH_SMD_4P_4.5x4.5x3.8MM - duplicate")
      (description "Switch Tactile N.O. SPST Round Button Gull Wing 0.05A 12VDC 100000Cycles 1.57N SMD T/R")
      (fields
        (field (name "MANUFACTURER PART NUMBER") "PTS645SM43SMTR92LFS")
        (field (name "LIBRARY MADE BY") "MR. XUAN SIEU")
      )
      (libsource (lib "LIBRARY2026") (part "SWITCH-SMD;4P,TACTILE,4.5x4.5mm"))
    )
    (comp (ref "SW3")
      (value "4.5x4.5")
      (footprint "SWITCH_SMD_4P_4.5x4.5x3.8MM - duplicate")
      (description "Switch Tactile N.O. SPST Round Button Gull Wing 0.05A 12VDC 100000Cycles 1.57N SMD T/R")
      (fields
        (field (name "MANUFACTURER PART NUMBER") "PTS645SM43SMTR92LFS")
        (field (name "LIBRARY MADE BY") "MR. XUAN SIEU")
      )
      (libsource (lib "LIBRARY2026") (part "SWITCH-SMD;4P,TACTILE,4.5x4.5mm"))
    )
    (comp (ref "SW4")
      (value "4.5x4.5")
      (footprint "SWITCH_SMD_4P_4.5x4.5x3.8MM - duplicate")
      (description "Switch Tactile N.O. SPST Round Button Gull Wing 0.05A 12VDC 100000Cycles 1.57N SMD T/R")
      (fields
        (field (name "MANUFACTURER PART NUMBER") "PTS645SM43SMTR92LFS")
        (field (name "LIBRARY MADE BY") "MR. XUAN SIEU")
      )
      (libsource (lib "LIBRARY2026") (part "SWITCH-SMD;4P,TACTILE,4.5x4.5mm"))
    )
    (comp (ref "SW5")
      (value "4.5x4.5")
      (footprint "SWITCH_SMD_4P_4.5x4.5x3.8MM - duplicate")
      (description "Switch Tactile N.O. SPST Round Button Gull Wing 0.05A 12VDC 100000Cycles 1.57N SMD T/R")
      (fields
        (field (name "MANUFACTURER PART NUMBER") "PTS645SM43SMTR92LFS")
        (field (name "LIBRARY MADE BY") "MR. XUAN SIEU")
      )
      (libsource (lib "LIBRARY2026") (part "SWITCH-SMD;4P,TACTILE,4.5x4.5mm"))
    )
    (comp (ref "SW6")
      (value "4.5x4.5")
      (footprint "SWITCH_SMD_4P_4.5x4.5x3.8MM - duplicate")
      (description "Switch Tactile N.O. SPST Round Button Gull Wing 0.05A 12VDC 100000Cycles 1.57N SMD T/R")
      (fields
        (field (name "MANUFACTURER PART NUMBER") "PTS645SM43SMTR92LFS")
        (field (name "LIBRARY MADE BY") "MR. XUAN SIEU")
      )
      (libsource (lib "LIBRARY2026") (part "SWITCH-SMD;4P,TACTILE,4.5x4.5mm"))
    )
    (comp (ref "SW7")
      (value "4.5x4.5")
      (footprint "SWITCH_SMD_4P_4.5x4.5x3.8MM - duplicate")
      (description "Switch Tactile N.O. SPST Round Button Gull Wing 0.05A 12VDC 100000Cycles 1.57N SMD T/R")
      (fields
        (field (name "MANUFACTURER PART NUMBER") "PTS645SM43SMTR92LFS")
        (field (name "LIBRARY MADE BY") "MR. XUAN SIEU")
      )
      (libsource (lib "LIBRARY2026") (part "SWITCH-SMD;4P,TACTILE,4.5x4.5mm"))
    )
    (comp (ref "SW8")
      (value "4.5x4.5")
      (footprint "SWITCH_SMD_4P_4.5x4.5x3.8MM - duplicate")
      (description "Switch Tactile N.O. SPST Round Button Gull Wing 0.05A 12VDC 100000Cycles 1.57N SMD T/R")
      (fields
        (field (name "MANUFACTURER PART NUMBER") "PTS645SM43SMTR92LFS")
        (field (name "LIBRARY MADE BY") "MR. XUAN SIEU")
      )
      (libsource (lib "LIBRARY2026") (part "SWITCH-SMD;4P,TACTILE,4.5x4.5mm"))
    )
    (comp (ref "SW9")
      (value "4.5x4.5")
      (footprint "SWITCH_SMD_4P_4.5x4.5x3.8MM - duplicate")
      (description "Switch Tactile N.O. SPST Round Button Gull Wing 0.05A 12VDC 100000Cycles 1.57N SMD T/R")
      (fields
        (field (name "MANUFACTURER PART NUMBER") "PTS645SM43SMTR92LFS")
        (field (name "LIBRARY MADE BY") "MR. XUAN SIEU")
      )
      (libsource (lib "LIBRARY2026") (part "SWITCH-SMD;4P,TACTILE,4.5x4.5mm"))
    )
    (comp (ref "SW10")
      (value "4.5x4.5")
      (footprint "SWITCH_SMD_4P_4.5x4.5x3.8MM - duplicate")
      (description "Switch Tactile N.O. SPST Round Button Gull Wing 0.05A 12VDC 100000Cycles 1.57N SMD T/R")
      (fields
        (field (name "MANUFACTURER PART NUMBER") "PTS645SM43SMTR92LFS")
        (field (name "LIBRARY MADE BY") "MR. XUAN SIEU")
      )
      (libsource (lib "LIBRARY2026") (part "SWITCH-SMD;4P,TACTILE,4.5x4.5mm"))
    )
    (comp (ref "SW11")
      (value "4.5x4.5")
      (footprint "SWITCH_SMD_4P_4.5x4.5x3.8MM - duplicate")
      (description "Switch Tactile N.O. SPST Round Button Gull Wing 0.05A 12VDC 100000Cycles 1.57N SMD T/R")
      (fields
        (field (name "MANUFACTURER PART NUMBER") "PTS645SM43SMTR92LFS")
        (field (name "LIBRARY MADE BY") "MR. XUAN SIEU")
      )
      (libsource (lib "LIBRARY2026") (part "SWITCH-SMD;4P,TACTILE,4.5x4.5mm"))
    )
    (comp (ref "SW12")
      (value "4.5x4.5")
      (footprint "SWITCH_SMD_4P_4.5x4.5x3.8MM - duplicate")
      (description "Switch Tactile N.O. SPST Round Button Gull Wing 0.05A 12VDC 100000Cycles 1.57N SMD T/R")
      (fields
        (field (name "MANUFACTURER PART NUMBER") "PTS645SM43SMTR92LFS")
        (field (name "LIBRARY MADE BY") "MR. XUAN SIEU")
      )
      (libsource (lib "LIBRARY2026") (part "SWITCH-SMD;4P,TACTILE,4.5x4.5mm"))
    )
    (comp (ref "SW13")
      (value "4.5x4.5")
      (footprint "SWITCH_SMD_4P_4.5x4.5x3.8MM - duplicate")
      (description "Switch Tactile N.O. SPST Round Button Gull Wing 0.05A 12VDC 100000Cycles 1.57N SMD T/R")
      (fields
        (field (name "MANUFACTURER PART NUMBER") "PTS645SM43SMTR92LFS")
        (field (name "LIBRARY MADE BY") "MR. XUAN SIEU")
      )
      (libsource (lib "LIBRARY2026") (part "SWITCH-SMD;4P,TACTILE,4.5x4.5mm"))
    )
    (comp (ref "T1")
      (value "SQ2389ES-T1_BE3")
      (footprint "SOT-23")
      (fields (field (name "MF") "Vishay"))
      (libsource (lib "SQ2389ES-T1_BE3") (part "SQ2389ES-T1_BE3"))
    )
    (comp (ref "U1")
      (value "LMR16006XDDCR")
      (footprint "SOT-6L")
      (description "SIMPLE SWITCHERÂ® 4V to 60V, 600mA Step-Down Regulator with Low Iq")
      (libsource (lib "PCB_NODE_2") (part "LMR16006XDDCR"))
    )
    (comp (ref "U2")
      (value "LMR16006XDDCR")
      (footprint "SOT-6L")
      (description "SIMPLE SWITCHERÂ® 4V to 60V, 600mA Step-Down Regulator with Low Iq")
      (libsource (lib "PCB_NODE_2") (part "LMR16006XDDCR"))
    )
    (comp (ref "U3")
      (value "MODULE_SAC_PIN_2S")
      (footprint "MODULE_SAC_PIN_2S")
      (libsource (lib "LIBRARY2026") (part "MODULE_SAC_PIN_2S"))
    )
    (comp (ref "U4")
      (value "STM32F103C8T6")
      (footprint "QFP50P900X900X160-48N")
      (description "ARM® Cortex®-M3 STM32F1 Microcontroller IC 32-Bit 72MHz 64KB (64K x 8) FLASH 48-LQFP (7x7)")
      (fields (field (name "MF") "STMicroelectronics"))
      (libsource (lib "LIBRARY2026") (part "STM32F103C8T6"))
    )
    (comp (ref "Y1")
      (value "ABL-8.000MHZ-B2")
      (footprint "XTAL_HC49P488W46L1150T500H350")
      (description "HC/49US (AT49) MICROPROCESSOR CRYSTAL")
      (fields (field (name "MP") "ABL-12.000MHZ-B2") (field (name "DIGI-KEY_PART_NUMBER") "535-9037-ND"))
      (libsource (lib "LIBRARY2026") (part "ABL-12.000MHZ-B2"))
    )
  )
  (nets
    (net (code "1") (name "+1.8V") (class "Default")
      (node (ref "C1") (pin "1") (pinfunction "1_1") (pintype "passive"))
      (node (ref "C9") (pin "1") (pinfunction "1_1") (pintype "passive"))
      (node (ref "M1") (pin "40") (pinfunction "VDD_EXT_40") (pintype "output"))
      (node (ref "R1") (pin "2") (pinfunction "2_2") (pintype "passive"))
      (node (ref "R2") (pin "2") (pinfunction "2_2") (pintype "passive"))
      (node (ref "R7") (pin "2") (pinfunction "2_2") (pintype "passive"))
      (node (ref "R8") (pin "2") (pinfunction "2_2") (pintype "passive"))
    )
    (net (code "2") (name "+3V3_DISPLAY") (class "Default")
      (node (ref "C22") (pin "2") (pinfunction "2_2") (pintype "passive"))
      (node (ref "J10") (pin "2") (pinfunction "2_2") (pintype "passive"))
      (node (ref "J11") (pin "2") (pinfunction "2_2") (pintype "passive"))
      (node (ref "J11") (pin "8") (pinfunction "8_8") (pintype "passive"))
      (node (ref "R21") (pin "2") (pinfunction "2_2") (pintype "passive"))
      (node (ref "R24") (pin "2") (pinfunction "2_2") (pintype "passive"))
    )
    (net (code "3") (name "+3V3_STM32") (class "Default")
      (node (ref "C12") (pin "2") (pinfunction "2_2") (pintype "passive"))
      (node (ref "C33") (pin "1") (pinfunction "1_1") (pintype "passive"))
      (node (ref "C34") (pin "1") (pinfunction "1_1") (pintype "passive"))
      (node (ref "C35") (pin "1") (pinfunction "1_1") (pintype "passive"))
      (node (ref "C40") (pin "2") (pinfunction "2_2") (pintype "passive"))
      (node (ref "C41") (pin "2") (pinfunction "2_2") (pintype "passive"))
      (node (ref "C42") (pin "2") (pinfunction "2_2") (pintype "passive"))
      (node (ref "C43") (pin "2") (pinfunction "2_2") (pintype "passive"))
      (node (ref "C45") (pin "2") (pinfunction "2_2") (pintype "passive"))
      (node (ref "C46") (pin "2") (pinfunction "2_2") (pintype "passive"))
      (node (ref "C47") (pin "2") (pinfunction "2_2") (pintype "passive"))
      (node (ref "C48") (pin "2") (pinfunction "2_2") (pintype "passive"))
      (node (ref "C8") (pin "1") (pinfunction "1_1") (pintype "passive"))
      (node (ref "DEBUG1") (pin "1") (pinfunction "1_1") (pintype "passive"))
      (node (ref "J12") (pin "1") (pinfunction "1_1") (pintype "passive"))
      (node (ref "J2") (pin "3") (pinfunction "3_3") (pintype "passive"))
      (node (ref "J3") (pin "3") (pinfunction "3_3") (pintype "passive"))
      (node (ref "J4") (pin "3") (pinfunction "3_3") (pintype "passive"))
      (node (ref "J5") (pin "3") (pinfunction "3_3") (pintype "passive"))
      (node (ref "J6") (pin "3") (pinfunction "3_3") (pintype "passive"))
      (node (ref "J7") (pin "3") (pinfunction "3_3") (pintype "passive"))
      (node (ref "J8") (pin "3") (pinfunction "3_3") (pintype "passive"))
      (node (ref "R11") (pin "2") (pinfunction "2_2") (pintype "passive"))
      (node (ref "R26") (pin "2") (pinfunction "2_2") (pintype "passive"))
      (node (ref "R32") (pin "2") (pinfunction "2_2") (pintype "passive"))
      (node (ref "R37") (pin "2") (pinfunction "2_2") (pintype "passive"))
      (node (ref "R38") (pin "2") (pinfunction "2_2") (pintype "passive"))
      (node (ref "R4") (pin "2") (pinfunction "2_2") (pintype "passive"))
      (node (ref "R40") (pin "2") (pinfunction "2_2") (pintype "passive"))
      (node (ref "R5") (pin "2") (pinfunction "2_2") (pintype "passive"))
      (node (ref "R9") (pin "2") (pinfunction "2_2") (pintype "passive"))
      (node (ref "RC1") (pin "1") (pinfunction "1_1") (pintype "passive"))
      (node (ref "U4") (pin "24") (pinfunction "VDD_24") (pintype "power_in"))
      (node (ref "U4") (pin "36") (pinfunction "VDD_36") (pintype "power_in"))
      (node (ref "U4") (pin "48") (pinfunction "VDD_48") (pintype "power_in"))
      (node (ref "U4") (pin "9") (pinfunction "VDDA_9") (pintype "power_in"))
    )
    (net (code "4") (name "+3V9_SIM") (class "Default")
      (node (ref "C27") (pin "2") (pinfunction "2_2") (pintype "passive"))
      (node (ref "C28") (pin "1") (pinfunction "1_1") (pintype "passive"))
      (node (ref "C29") (pin "1") (pinfunction "1_1") (pintype "passive"))
      (node (ref "C30") (pin "1") (pinfunction "1_1") (pintype "passive"))
      (node (ref "C31") (pin "1") (pinfunction "1_1") (pintype "passive"))
      (node (ref "D1") (pin "2") (pinfunction "K_2") (pintype "passive"))
      (node (ref "D3") (pin "1") (pinfunction "A_1") (pintype "passive"))
      (node (ref "D4") (pin "1") (pinfunction "A_1") (pintype "passive"))
      (node (ref "L1") (pin "2") (pinfunction "2_2") (pintype "passive"))
      (node (ref "L4") (pin "2") (pinfunction "2_2") (pintype "passive"))
      (node (ref "R33") (pin "2") (pinfunction "2_2") (pintype "passive"))
      (node (ref "R34") (pin "2") (pinfunction "2_2") (pintype "passive"))
    )
    (net (code "5") (name "/ADCX_L") (class "Default")
      (node (ref "J4") (pin "2") (pinfunction "2_2") (pintype "passive"))
      (node (ref "U4") (pin "16") (pinfunction "PA6_16") (pintype "bidirectional"))
    )
    (net (code "6") (name "/ADCX_R") (class "Default")
      (node (ref "J7") (pin "2") (pinfunction "2_2") (pintype "passive"))
      (node (ref "U4") (pin "19") (pinfunction "PB1_19") (pintype "bidirectional"))
    )
    (net (code "7") (name "/ADCY_L") (class "Default")
      (node (ref "J2") (pin "2") (pinfunction "2_2") (pintype "passive"))
      (node (ref "U4") (pin "18") (pinfunction "PB0_18") (pintype "bidirectional"))
    )
    (net (code "8") (name "/ADCY_R") (class "Default")
      (node (ref "J6") (pin "2") (pinfunction "2_2") (pintype "passive"))
      (node (ref "U4") (pin "17") (pinfunction "PA7_17") (pintype "bidirectional"))
    )
    (net (code "9") (name "/BATM") (class "Default")
      (node (ref "J1") (pin "2") (pinfunction "2_2") (pintype "passive"))
    )
    (net (code "10") (name "/BAT_ADC") (class "Default")
      (node (ref "R45") (pin "2") (pinfunction "2_2") (pintype "passive"))
      (node (ref "U4") (pin "11") (pinfunction "PA1_11") (pintype "bidirectional"))
    )
    (net (code "11") (name "/BAT_IN") (class "Default")
      (node (ref "J1") (pin "1") (pinfunction "1_1") (pintype "passive"))
      (node (ref "T1") (pin "2") (pinfunction "S_2") (pintype "passive"))
      (node (ref "U3") (pin "BAT") (pinfunction "BAT_BAT") (pintype "passive"))
    )
    (net (code "12") (name "/BOOT_STM32") (class "Default")
      (node (ref "R39") (pin "1") (pinfunction "1_1") (pintype "passive"))
      (node (ref "U4") (pin "44") (pinfunction "BOOT0_44") (pintype "input"))
    )
    (net (code "13") (name "/BUZZ") (class "Default")
      (node (ref "R42") (pin "1") (pinfunction "1_1") (pintype "passive"))
      (node (ref "U4") (pin "33") (pinfunction "PA12_33") (pintype "bidirectional"))
    )
    (net (code "14") (name "/COL_1") (class "Default")
      (node (ref "SW1") (pin "2") (pinfunction "2_2") (pintype "passive"))
      (node (ref "SW5") (pin "2") (pinfunction "2_2") (pintype "passive"))
      (node (ref "SW9") (pin "2") (pinfunction "2_2") (pintype "passive"))
      (node (ref "U4") (pin "45") (pinfunction "PB8_45") (pintype "bidirectional"))
    )
    (net (code "15") (name "/COL_2") (class "Default")
      (node (ref "SW10") (pin "2") (pinfunction "2_2") (pintype "passive"))
      (node (ref "SW2") (pin "2") (pinfunction "2_2") (pintype "passive"))
      (node (ref "SW6") (pin "2") (pinfunction "2_2") (pintype "passive"))
      (node (ref "U4") (pin "43") (pinfunction "PB7_43") (pintype "bidirectional"))
    )
    (net (code "16") (name "/COL_3") (class "Default")
      (node (ref "SW11") (pin "2") (pinfunction "2_2") (pintype "passive"))
      (node (ref "SW3") (pin "2") (pinfunction "2_2") (pintype "passive"))
      (node (ref "SW7") (pin "2") (pinfunction "2_2") (pintype "passive"))
      (node (ref "U4") (pin "42") (pinfunction "PB6_42") (pintype "bidirectional"))
    )
    (net (code "17") (name "/COL_4") (class "Default")
      (node (ref "SW12") (pin "2") (pinfunction "2_2") (pintype "passive"))
      (node (ref "SW4") (pin "2") (pinfunction "2_2") (pintype "passive"))
      (node (ref "SW8") (pin "2") (pinfunction "2_2") (pintype "passive"))
      (node (ref "U4") (pin "41") (pinfunction "PB5_41") (pintype "bidirectional"))
    )
    (net (code "18") (name "/DC") (class "Default")
      (node (ref "J11") (pin "6") (pinfunction "6_6") (pintype "passive"))
      (node (ref "U4") (pin "27") (pinfunction "PB14_27") (pintype "bidirectional"))
    )
    (net (code "19") (name "/LED_1") (class "Default")
      (node (ref "R41") (pin "2") (pinfunction "2_2") (pintype "passive"))
      (node (ref "U4") (pin "32") (pinfunction "PA11_32") (pintype "bidirectional"))
    )
    (net (code "20") (name "/OSC_IN") (class "Default")
      (node (ref "C36") (pin "1") (pinfunction "1_1") (pintype "passive"))
      (node (ref "U4") (pin "5") (pinfunction "PD0_OSC_IN_5") (pintype "bidirectional"))
      (node (ref "Y1") (pin "2") (pinfunction "2_2") (pintype "passive"))
    )
    (net (code "21") (name "/OSC_OUT") (class "Default")
      (node (ref "C39") (pin "1") (pinfunction "1_1") (pintype "passive"))
      (node (ref "U4") (pin "6") (pinfunction "PD1_OSC_OUT_6") (pintype "bidirectional"))
      (node (ref "Y1") (pin "1") (pinfunction "1_1") (pintype "passive"))
    )
    (net (code "22") (name "/RESET_LCD") (class "Default")
      (node (ref "J11") (pin "5") (pinfunction "5_5") (pintype "passive"))
      (node (ref "U4") (pin "29") (pinfunction "PA8_29") (pintype "bidirectional"))
    )
    (net (code "23") (name "/RESET_SIM") (class "Default")
      (node (ref "R29") (pin "2") (pinfunction "2_2") (pintype "passive"))
      (node (ref "U4") (pin "20") (pinfunction "PB2_20") (pintype "bidirectional"))
    )
    (net (code "24") (name "/RESET_SMT32") (class "Default")
      (node (ref "BUT1") (pin "2") (pinfunction "2_2") (pintype "passive"))
      (node (ref "C37") (pin "1") (pinfunction "1_1") (pintype "passive"))
      (node (ref "R38") (pin "1") (pinfunction "1_1") (pintype "passive"))
      (node (ref "U4") (pin "7") (pinfunction "NRST_7") (pintype "input"))
    )
    (net (code "25") (name "/ROW_1") (class "Default")
      (node (ref "R11") (pin "1") (pinfunction "1_1") (pintype "passive"))
      (node (ref "SW1") (pin "3") (pinfunction "3_3") (pintype "passive"))
      (node (ref "U4") (pin "40") (pinfunction "PB4_40") (pintype "bidirectional"))
    )
    (net (code "26") (name "/ROW_2") (class "Default")
      (node (ref "R26") (pin "1") (pinfunction "1_1") (pintype "passive"))
      (node (ref "SW5") (pin "3") (pinfunction "3_3") (pintype "passive"))
      (node (ref "U4") (pin "39") (pinfunction "PB3_39") (pintype "bidirectional"))
    )
    (net (code "27") (name "/ROW_3") (class "Default")
      (node (ref "R32") (pin "1") (pinfunction "1_1") (pintype "passive"))
      (node (ref "SW9") (pin "3") (pinfunction "3_3") (pintype "passive"))
      (node (ref "U4") (pin "38") (pinfunction "PA15_38") (pintype "bidirectional"))
    )
    (net (code "28") (name "/RXD_MODULE_SIM") (class "Default")
      (node (ref "M1") (pin "2") (pinfunction "RXD_2") (pintype "input"))
      (node (ref "Q1") (pin "3") (pinfunction "C_3") (pintype "passive"))
      (node (ref "R2") (pin "1") (pinfunction "1_1") (pintype "passive"))
    )
    (net (code "29") (name "/RX_MCU_1") (class "Default")
      (node (ref "C8") (pin "2") (pinfunction "2_2") (pintype "passive"))
      (node (ref "Q2") (pin "3") (pinfunction "C_3") (pintype "passive"))
      (node (ref "R5") (pin "1") (pinfunction "1_1") (pintype "passive"))
      (node (ref "U4") (pin "13") (pinfunction "PA3_13") (pintype "bidirectional"))
    )
    (net (code "30") (name "/RX_MCU_2") (class "Default")
      (node (ref "J12") (pin "3") (pinfunction "3_3") (pintype "passive"))
      (node (ref "U4") (pin "31") (pinfunction "PA10_31") (pintype "bidirectional"))
    )
    (net (code "31") (name "/SCL_LCD") (class "Default")
      (node (ref "J10") (pin "3") (pinfunction "3_3") (pintype "passive"))
      (node (ref "U4") (pin "21") (pinfunction "PB10_21") (pintype "bidirectional"))
    )
    (net (code "32") (name "/SDA_LCD") (class "Default")
      (node (ref "J10") (pin "4") (pinfunction "4_4") (pintype "passive"))
      (node (ref "U4") (pin "22") (pinfunction "PB11_22") (pintype "bidirectional"))
    )
    (net (code "33") (name "/SPI_MOSI") (class "Default")
      (node (ref "J11") (pin "4") (pinfunction "4_4") (pintype "passive"))
      (node (ref "U4") (pin "28") (pinfunction "PB15_28") (pintype "bidirectional"))
    )
    (net (code "34") (name "/SPI_SCK") (class "Default")
      (node (ref "J11") (pin "3") (pinfunction "3_3") (pintype "passive"))
      (node (ref "U4") (pin "26") (pinfunction "PB13_26") (pintype "bidirectional"))
    )
    (net (code "35") (name "/SWCLK") (class "Default")
      (node (ref "DEBUG1") (pin "4") (pinfunction "4_4") (pintype "passive"))
      (node (ref "U4") (pin "37") (pinfunction "PA14_37") (pintype "bidirectional"))
    )
    (net (code "36") (name "/SWDIO") (class "Default")
      (node (ref "DEBUG1") (pin "3") (pinfunction "3_3") (pintype "passive"))
      (node (ref "U4") (pin "34") (pinfunction "PA13_34") (pintype "bidirectional"))
    )
    (net (code "37") (name "/SW_2P_L") (class "Default")
      (node (ref "J3") (pin "2") (pinfunction "2_2") (pintype "passive"))
      (node (ref "U4") (pin "46") (pinfunction "PB9_46") (pintype "bidirectional"))
    )
    (net (code "38") (name "/SW_2P_R") (class "Default")
      (node (ref "J5") (pin "4") (pinfunction "4_4") (pintype "passive"))
      (node (ref "U4") (pin "4") (pinfunction "PC15-OSC32_OUT_4") (pintype "bidirectional"))
    )
    (net (code "39") (name "/SW_3P_L") (class "Default")
      (node (ref "J3") (pin "4") (pinfunction "4_4") (pintype "passive"))
      (node (ref "U4") (pin "2") (pinfunction "PC13-TAMPER-RTC_2") (pintype "bidirectional"))
    )
    (net (code "40") (name "/SW_3P_R") (class "Default")
      (node (ref "J5") (pin "2") (pinfunction "2_2") (pintype "passive"))
      (node (ref "U4") (pin "3") (pinfunction "PC14-OSC32_IN_3") (pintype "bidirectional"))
    )
    (net (code "41") (name "/TXD_MODULE_SIM") (class "Default")
      (node (ref "M1") (pin "1") (pinfunction "TXD_1") (pintype "output"))
      (node (ref "Q2") (pin "2") (pinfunction "E_2") (pintype "passive"))
    )
    (net (code "42") (name "/TX_MCU_1") (class "Default")
      (node (ref "Q1") (pin "2") (pinfunction "E_2") (pintype "passive"))
      (node (ref "U4") (pin "12") (pinfunction "PA2_12") (pintype "bidirectional"))
    )
    (net (code "43") (name "/TX_MCU_2") (class "Default")
      (node (ref "J12") (pin "2") (pinfunction "2_2") (pintype "passive"))
      (node (ref "U4") (pin "30") (pinfunction "PA9_30") (pintype "bidirectional"))
    )
    (net (code "44") (name "/USIM_DT") (class "Default")
      (node (ref "M1") (pin "14") (pinfunction "USIM_DET_14") (pintype "input"))
      (node (ref "R12") (pin "2") (pinfunction "2_2") (pintype "passive"))
      (node (ref "R8") (pin "1") (pinfunction "1_1") (pintype "passive"))
    )
    (net (code "45") (name "/VIN") (class "Default")
      (node (ref "J9") (pin "A9") (pinfunction "VBUS_A9") (pintype "power_in"))
      (node (ref "J9") (pin "B9") (pinfunction "VBUS_B9") (pintype "power_in"))
      (node (ref "U3") (pin "VIN") (pinfunction "VIN_VIN") (pintype "passive"))
    )
    (net (code "46") (name "/VRA") (class "Default")
      (node (ref "J8") (pin "2") (pinfunction "2_2") (pintype "passive"))
      (node (ref "U4") (pin "15") (pinfunction "PA5_15") (pintype "bidirectional"))
    )
    (net (code "47") (name "/VRB") (class "Default")
      (node (ref "J8") (pin "4") (pinfunction "4_4") (pintype "passive"))
      (node (ref "U4") (pin "14") (pinfunction "PA4_14") (pintype "bidirectional"))
    )
    (net (code "48") (name "/WKUP") (class "Default")
      (node (ref "C32") (pin "1") (pinfunction "1_1") (pintype "passive"))
      (node (ref "R37") (pin "1") (pinfunction "1_1") (pintype "passive"))
      (node (ref "SW13") (pin "2") (pinfunction "2_2") (pintype "passive"))
      (node (ref "U4") (pin "10") (pinfunction "PA0_WKUP_10") (pintype "bidirectional"))
    )
    (net (code "49") (name "BAT+") (class "Default")
      (node (ref "C10") (pin "1") (pinfunction "1_1") (pintype "passive"))
      (node (ref "C11") (pin "2") (pinfunction "2_2") (pintype "passive"))
      (node (ref "C20") (pin "1") (pinfunction "1_1") (pintype "passive"))
      (node (ref "C21") (pin "2") (pinfunction "2_2") (pintype "passive"))
      (node (ref "C24") (pin "2") (pinfunction "2_2") (pintype "passive"))
      (node (ref "C25") (pin "2") (pinfunction "2_2") (pintype "passive"))
      (node (ref "IC1") (pin "3") (pinfunction "VIN_3") (pintype "input"))
      (node (ref "R20") (pin "2") (pinfunction "2_2") (pintype "passive"))
      (node (ref "R3") (pin "2") (pinfunction "2_2") (pintype "passive"))
      (node (ref "R31") (pin "1") (pinfunction "1_1") (pintype "passive"))
      (node (ref "R44") (pin "2") (pinfunction "2_2") (pintype "passive"))
      (node (ref "T1") (pin "3") (pinfunction "D_3") (pintype "passive"))
      (node (ref "U1") (pin "5") (pinfunction "VIN_5") (pintype "input"))
      (node (ref "U2") (pin "5") (pinfunction "VIN_5") (pintype "input"))
    )
    (net (code "50") (name "GND") (class "Default")
      (node (ref "1") (pin "C5") (pinfunction "GND_C5") (pintype "power_in"))
      (node (ref "1") (pin "G1") (pinfunction "GND_G1") (pintype "power_in"))
      (node (ref "1") (pin "G2") (pinfunction "GND_G2") (pintype "power_in"))
      (node (ref "1") (pin "G3") (pinfunction "GND_G3") (pintype "power_in"))
      (node (ref "1") (pin "G4") (pinfunction "GND_G4") (pintype "power_in"))
      (node (ref "AT1") (pin "2") (pinfunction "GND_2") (pintype "passive"))
      (node (ref "BUT1") (pin "1") (pinfunction "1_1") (pintype "passive"))
      (node (ref "C10") (pin "2") (pinfunction "2_2") (pintype "passive"))
      (node (ref "C11") (pin "1") (pinfunction "1_1") (pintype "passive"))
      (node (ref "C12") (pin "1") (pinfunction "1_1") (pintype "passive"))
      (node (ref "C13") (pin "1") (pinfunction "1_1") (pintype "passive"))
      (node (ref "C14") (pin "1") (pinfunction "1_1") (pintype "passive"))
      (node (ref "C15") (pin "2") (pinfunction "2_2") (pintype "passive"))
      (node (ref "C17") (pin "2") (pinfunction "2_2") (pintype "passive"))
      (node (ref "C18") (pin "2") (pinfunction "2_2") (pintype "passive"))
      (node (ref "C19") (pin "2") (pinfunction "2_2") (pintype "passive"))
      (node (ref "C2") (pin "1") (pinfunction "1_1") (pintype "passive"))
      (node (ref "C20") (pin "2") (pinfunction "2_2") (pintype "passive"))
      (node (ref "C21") (pin "1") (pinfunction "1_1") (pintype "passive"))
      (node (ref "C22") (pin "1") (pinfunction "1_1") (pintype "passive"))
      (node (ref "C23") (pin "2") (pinfunction "2_2") (pintype "passive"))
      (node (ref "C24") (pin "1") (pinfunction "1_1") (pintype "passive"))
      (node (ref "C25") (pin "1") (pinfunction "1_1") (pintype "passive"))
      (node (ref "C28") (pin "2") (pinfunction "2_2") (pintype "passive"))
      (node (ref "C29") (pin "2") (pinfunction "2_2") (pintype "passive"))
      (node (ref "C3") (pin "1") (pinfunction "1_1") (pintype "passive"))
      (node (ref "C30") (pin "2") (pinfunction "2_2") (pintype "passive"))
      (node (ref "C31") (pin "2") (pinfunction "2_2") (pintype "passive"))
      (node (ref "C32") (pin "2") (pinfunction "2_2") (pintype "passive"))
      (node (ref "C33") (pin "2") (pinfunction "2_2") (pintype "passive"))
      (node (ref "C34") (pin "2") (pinfunction "2_2") (pintype "passive"))
      (node (ref "C35") (pin "2") (pinfunction "2_2") (pintype "passive"))
      (node (ref "C36") (pin "2") (pinfunction "2_2") (pintype "passive"))
      (node (ref "C37") (pin "2") (pinfunction "2_2") (pintype "passive"))
      (node (ref "C39") (pin "2") (pinfunction "2_2") (pintype "passive"))
      (node (ref "C4") (pin "1") (pinfunction "1_1") (pintype "passive"))
      (node (ref "C40") (pin "1") (pinfunction "1_1") (pintype "passive"))
      (node (ref "C41") (pin "1") (pinfunction "1_1") (pintype "passive"))
      (node (ref "C42") (pin "1") (pinfunction "1_1") (pintype "passive"))
      (node (ref "C43") (pin "1") (pinfunction "1_1") (pintype "passive"))
      (node (ref "C44") (pin "2") (pinfunction "2_2") (pintype "passive"))
      (node (ref "C45") (pin "1") (pinfunction "1_1") (pintype "passive"))
      (node (ref "C46") (pin "1") (pinfunction "1_1") (pintype "passive"))
      (node (ref "C47") (pin "1") (pinfunction "1_1") (pintype "passive"))
      (node (ref "C48") (pin "1") (pinfunction "1_1") (pintype "passive"))
      (node (ref "C5") (pin "1") (pinfunction "1_1") (pintype "passive"))
      (node (ref "C6") (pin "1") (pinfunction "1_1") (pintype "passive"))
      (node (ref "D1") (pin "1") (pinfunction "A_1") (pintype "passive"))
      (node (ref "D2") (pin "1") (pinfunction "1_1") (pintype "passive"))
      (node (ref "D5") (pin "1") (pinfunction "1_1") (pintype "passive"))
      (node (ref "D6") (pin "1") (pinfunction "A_1") (pintype "passive"))
      (node (ref "D7") (pin "2") (pinfunction "K_2") (pintype "passive"))
      (node (ref "D8") (pin "2") (pinfunction "K_2") (pintype "passive"))
      (node (ref "D9") (pin "1") (pinfunction "A_1") (pintype "passive"))
      (node (ref "DEBUG1") (pin "2") (pinfunction "2_2") (pintype "passive"))
      (node (ref "EC1") (pin "2") (pinfunction "N_2") (pintype "passive"))
      (node (ref "EC2") (pin "2") (pinfunction "N_2") (pintype "passive"))
      (node (ref "IC1") (pin "1") (pinfunction "GND_1") (pintype "power_in"))
      (node (ref "J1") (pin "3") (pinfunction "3_3") (pintype "passive"))
      (node (ref "J10") (pin "1") (pinfunction "1_1") (pintype "passive"))
      (node (ref "J11") (pin "1") (pinfunction "1_1") (pintype "passive"))
      (node (ref "J11") (pin "7") (pinfunction "7_7") (pintype "passive"))
      (node (ref "J12") (pin "4") (pinfunction "4_4") (pintype "passive"))
      (node (ref "J2") (pin "1") (pinfunction "1_1") (pintype "passive"))
      (node (ref "J3") (pin "1") (pinfunction "1_1") (pintype "passive"))
      (node (ref "J4") (pin "1") (pinfunction "1_1") (pintype "passive"))
      (node (ref "J5") (pin "1") (pinfunction "1_1") (pintype "passive"))
      (node (ref "J6") (pin "1") (pinfunction "1_1") (pintype "passive"))
      (node (ref "J7") (pin "1") (pinfunction "1_1") (pintype "passive"))
      (node (ref "J8") (pin "1") (pinfunction "1_1") (pintype "passive"))
      (node (ref "J9") (pin "0") (pinfunction "0_0") (pintype "passive"))
      (node (ref "J9") (pin "A12") (pinfunction "GND_A12") (pintype "power_in"))
      (node (ref "J9") (pin "B12") (pinfunction "GND_B12") (pintype "power_in"))
      (node (ref "M1") (pin "13") (pinfunction "GND_13") (pintype "power_in"))
      (node (ref "M1") (pin "19") (pinfunction "GND_19") (pintype "power_in"))
      (node (ref "M1") (pin "21") (pinfunction "GND_21") (pintype "power_in"))
      (node (ref "M1") (pin "27") (pinfunction "GND_27") (pintype "power_in"))
      (node (ref "M1") (pin "30") (pinfunction "GND_30") (pintype "power_in"))
      (node (ref "M1") (pin "31") (pinfunction "GND_31") (pintype "power_in"))
      (node (ref "M1") (pin "33") (pinfunction "GND_33") (pintype "power_in"))
      (node (ref "M1") (pin "36") (pinfunction "GND_36") (pintype "power_in"))
      (node (ref "M1") (pin "37") (pinfunction "GND_37") (pintype "power_in"))
      (node (ref "M1") (pin "8") (pinfunction "GND_8") (pintype "power_in"))
      (node (ref "M1") (pin "87") (pinfunction "GND_87") (pintype "power_in"))
      (node (ref "M1") (pin "88") (pinfunction "GND_88") (pintype "power_in"))
      (node (ref "M1") (pin "89") (pinfunction "GND_89") (pintype "power_in"))
      (node (ref "M1") (pin "90") (pinfunction "GND_90") (pintype "power_in"))
      (node (ref "M1") (pin "91") (pinfunction "GND_91") (pintype "power_in"))
      (node (ref "M1") (pin "92") (pinfunction "GND_92") (pintype "power_in"))
      (node (ref "PWR_DISPLAY1") (pin "2") (pinfunction "2_2") (pintype "passive"))
      (node (ref "PWR_STM1") (pin "2") (pinfunction "2_2") (pintype "passive"))
      (node (ref "Q3") (pin "2") (pinfunction "E_2") (pintype "passive"))
      (node (ref "Q4") (pin "2") (pinfunction "E_2") (pintype "passive"))
      (node (ref "Q5") (pin "2") (pinfunction "E_2") (pintype "passive"))
      (node (ref "Q6") (pin "2") (pinfunction "E_2") (pintype "passive"))
      (node (ref "R10") (pin "1") (pinfunction "1_1") (pintype "passive"))
      (node (ref "R18") (pin "1") (pinfunction "1_1") (pintype "passive"))
      (node (ref "R25") (pin "1") (pinfunction "1_1") (pintype "passive"))
      (node (ref "R27") (pin "1") (pinfunction "1_1") (pintype "passive"))
      (node (ref "R28") (pin "1") (pinfunction "1_1") (pintype "passive"))
      (node (ref "R30") (pin "1") (pinfunction "1_1") (pintype "passive"))
      (node (ref "R35") (pin "1") (pinfunction "1_1") (pintype "passive"))
      (node (ref "R36") (pin "1") (pinfunction "1_1") (pintype "passive"))
      (node (ref "R39") (pin "2") (pinfunction "2_2") (pintype "passive"))
      (node (ref "R43") (pin "1") (pinfunction "1_1") (pintype "passive"))
      (node (ref "R46") (pin "1") (pinfunction "1_1") (pintype "passive"))
      (node (ref "SW13") (pin "3") (pinfunction "3_3") (pintype "passive"))
      (node (ref "U1") (pin "2") (pinfunction "GND_2") (pintype "power_in"))
      (node (ref "U2") (pin "2") (pinfunction "GND_2") (pintype "power_in"))
      (node (ref "U3") (pin "GND") (pinfunction "GND_GND") (pintype "passive"))
      (node (ref "U4") (pin "23") (pinfunction "VSS_23") (pintype "power_in"))
      (node (ref "U4") (pin "35") (pinfunction "VSS_35") (pintype "power_in"))
      (node (ref "U4") (pin "47") (pinfunction "VSS_47") (pintype "power_in"))
      (node (ref "U4") (pin "8") (pinfunction "VSSA_8") (pintype "power_in"))
    )
    (net (code "51") (name "Net-(1-CLK)") (class "Default")
      (node (ref "1") (pin "C3") (pinfunction "CLK_C3") (pintype "input"))
      (node (ref "C17") (pin "1") (pinfunction "1_1") (pintype "passive"))
      (node (ref "R14") (pin "1") (pinfunction "1_1") (pintype "passive"))
    )
    (net (code "52") (name "Net-(1-I{slash}O)") (class "Default")
      (node (ref "1") (pin "C7") (pinfunction "I/O_C7") (pintype "bidirectional"))
      (node (ref "C19") (pin "1") (pinfunction "1_1") (pintype "passive"))
      (node (ref "R16") (pin "1") (pinfunction "1_1") (pintype "passive"))
    )
    (net (code "53") (name "Net-(1-PadCD)") (class "Default")
      (node (ref "1") (pin "CD") (pinfunction "CD_CD") (pintype "bidirectional"))
      (node (ref "R12") (pin "1") (pinfunction "1_1") (pintype "passive"))
    )
    (net (code "54") (name "Net-(1-RST)") (class "Default")
      (node (ref "1") (pin "C2") (pinfunction "RST_C2") (pintype "input"))
      (node (ref "C18") (pin "1") (pinfunction "1_1") (pintype "passive"))
      (node (ref "R13") (pin "1") (pinfunction "1_1") (pintype "passive"))
    )
    (net (code "55") (name "Net-(1-VCC)") (class "Default")
      (node (ref "1") (pin "C1") (pinfunction "VCC_C1") (pintype "power_in"))
      (node (ref "C13") (pin "2") (pinfunction "2_2") (pintype "passive"))
      (node (ref "C14") (pin "2") (pinfunction "2_2") (pintype "passive"))
      (node (ref "C15") (pin "1") (pinfunction "1_1") (pintype "passive"))
      (node (ref "M1") (pin "18") (pinfunction "USIM_VDD_18") (pintype "passive"))
    )
    (net (code "56") (name "Net-(AT1-AT)") (class "Default")
      (node (ref "AT1") (pin "1") (pinfunction "AT_1") (pintype "passive"))
      (node (ref "M1") (pin "32") (pinfunction "RF_ANT_32") (pintype "passive"))
    )
    (net (code "57") (name "Net-(D3-K)") (class "Default")
      (node (ref "D3") (pin "2") (pinfunction "K_2") (pintype "passive"))
      (node (ref "R15") (pin "2") (pinfunction "2_2") (pintype "passive"))
    )
    (net (code "58") (name "Net-(D4-K)") (class "Default")
      (node (ref "D4") (pin "2") (pinfunction "K_2") (pintype "passive"))
      (node (ref "R17") (pin "2") (pinfunction "2_2") (pintype "passive"))
    )
    (net (code "59") (name "Net-(D6-K)") (class "Default")
      (node (ref "C23") (pin "1") (pinfunction "1_1") (pintype "passive"))
      (node (ref "D6") (pin "2") (pinfunction "K_2") (pintype "passive"))
      (node (ref "M1") (pin "29") (pinfunction "RESET_29") (pintype "input"))
      (node (ref "Q5") (pin "3") (pinfunction "C_3") (pintype "passive"))
    )
    (net (code "60") (name "Net-(D7-A)") (class "Default")
      (node (ref "D7") (pin "1") (pinfunction "A_1") (pintype "passive"))
      (node (ref "R33") (pin "1") (pinfunction "1_1") (pintype "passive"))
    )
    (net (code "61") (name "Net-(D8-A)") (class "Default")
      (node (ref "D8") (pin "1") (pinfunction "A_1") (pintype "passive"))
      (node (ref "R41") (pin "1") (pinfunction "1_1") (pintype "passive"))
    )
    (net (code "62") (name "Net-(D9-K)") (class "Default")
      (node (ref "C44") (pin "1") (pinfunction "1_1") (pintype "passive"))
      (node (ref "D9") (pin "2") (pinfunction "K_2") (pintype "passive"))
      (node (ref "R44") (pin "1") (pinfunction "1_1") (pintype "passive"))
      (node (ref "R45") (pin "1") (pinfunction "1_1") (pintype "passive"))
      (node (ref "R46") (pin "2") (pinfunction "2_2") (pintype "passive"))
    )
    (net (code "63") (name "Net-(EC1-P)") (class "Default")
      (node (ref "C2") (pin "2") (pinfunction "2_2") (pintype "passive"))
      (node (ref "C3") (pin "2") (pinfunction "2_2") (pintype "passive"))
      (node (ref "C4") (pin "2") (pinfunction "2_2") (pintype "passive"))
      (node (ref "C5") (pin "2") (pinfunction "2_2") (pintype "passive"))
      (node (ref "C6") (pin "2") (pinfunction "2_2") (pintype "passive"))
      (node (ref "EC1") (pin "1") (pinfunction "P_1") (pintype "passive"))
      (node (ref "EC2") (pin "1") (pinfunction "P_1") (pintype "passive"))
      (node (ref "L1") (pin "1") (pinfunction "1_1") (pintype "passive"))
      (node (ref "M1") (pin "34") (pinfunction "VBAT_34") (pintype "power_in"))
      (node (ref "M1") (pin "35") (pinfunction "VBAT_35") (pintype "power_in"))
    )
    (net (code "64") (name "Net-(IC1-BST)") (class "Default")
      (node (ref "C26") (pin "1") (pinfunction "1_1") (pintype "passive"))
      (node (ref "IC1") (pin "6") (pinfunction "BST_6") (pintype "input"))
    )
    (net (code "65") (name "Net-(IC1-EN)") (class "Default")
      (node (ref "IC1") (pin "5") (pinfunction "EN_5") (pintype "input"))
      (node (ref "R31") (pin "2") (pinfunction "2_2") (pintype "passive"))
    )
    (net (code "66") (name "Net-(IC1-FB)") (class "Default")
      (node (ref "C27") (pin "1") (pinfunction "1_1") (pintype "passive"))
      (node (ref "IC1") (pin "4") (pinfunction "FB_4") (pintype "input"))
      (node (ref "R34") (pin "1") (pinfunction "1_1") (pintype "passive"))
      (node (ref "R35") (pin "2") (pinfunction "2_2") (pintype "passive"))
    )
    (net (code "67") (name "Net-(IC1-SW)") (class "Default")
      (node (ref "C26") (pin "2") (pinfunction "2_2") (pintype "passive"))
      (node (ref "IC1") (pin "2") (pinfunction "SW_2") (pintype "output"))
      (node (ref "L4") (pin "1") (pinfunction "1_1") (pintype "passive"))
    )
    (net (code "68") (name "Net-(L2-Pad2)") (class "Default")
      (node (ref "L2") (pin "2") (pinfunction "2_2") (pintype "passive"))
      (node (ref "R4") (pin "1") (pinfunction "1_1") (pintype "passive"))
      (node (ref "R6") (pin "2") (pinfunction "2_2") (pintype "passive"))
    )
    (net (code "69") (name "Net-(L3-Pad2)") (class "Default")
      (node (ref "L3") (pin "2") (pinfunction "2_2") (pintype "passive"))
      (node (ref "R21") (pin "1") (pinfunction "1_1") (pintype "passive"))
      (node (ref "R22") (pin "2") (pinfunction "2_2") (pintype "passive"))
    )
    (net (code "70") (name "Net-(LS1-PadP)") (class "Default")
      (node (ref "LS1") (pin "P") (pinfunction "P_P") (pintype "passive"))
      (node (ref "R40") (pin "1") (pinfunction "1_1") (pintype "passive"))
    )
    (net (code "71") (name "Net-(M1-NETLIGHT)") (class "Default")
      (node (ref "M1") (pin "41") (pinfunction "NETLIGHT_41") (pintype "output"))
      (node (ref "R19") (pin "1") (pinfunction "1_1") (pintype "passive"))
    )
    (net (code "72") (name "Net-(M1-PWRKEY)") (class "Default")
      (node (ref "M1") (pin "39") (pinfunction "PWRKEY_39") (pintype "input"))
      (node (ref "R18") (pin "2") (pinfunction "2_2") (pintype "passive"))
    )
    (net (code "73") (name "Net-(M1-STATUS)") (class "Default")
      (node (ref "M1") (pin "42") (pinfunction "STATUS_42") (pintype "output"))
      (node (ref "R23") (pin "1") (pinfunction "1_1") (pintype "passive"))
    )
    (net (code "74") (name "Net-(M1-USIM_CLK)") (class "Default")
      (node (ref "M1") (pin "16") (pinfunction "USIM_CLK_16") (pintype "output"))
      (node (ref "R14") (pin "2") (pinfunction "2_2") (pintype "passive"))
    )
    (net (code "75") (name "Net-(M1-USIM_DATA)") (class "Default")
      (node (ref "M1") (pin "15") (pinfunction "USIM_DATA_15") (pintype "bidirectional"))
      (node (ref "R16") (pin "2") (pinfunction "2_2") (pintype "passive"))
    )
    (net (code "76") (name "Net-(M1-USIM_RST)") (class "Default")
      (node (ref "M1") (pin "17") (pinfunction "USIM_RST_17") (pintype "output"))
      (node (ref "R13") (pin "2") (pinfunction "2_2") (pintype "passive"))
    )
    (net (code "77") (name "Net-(PWR_DISPLAY1-Pad1)") (class "Default")
      (node (ref "PWR_DISPLAY1") (pin "1") (pinfunction "1_1") (pintype "passive"))
      (node (ref "R24") (pin "1") (pinfunction "1_1") (pintype "passive"))
    )
    (net (code "78") (name "Net-(PWR_STM1-Pad1)") (class "Default")
      (node (ref "PWR_STM1") (pin "1") (pinfunction "1_1") (pintype "passive"))
      (node (ref "R9") (pin "1") (pinfunction "1_1") (pintype "passive"))
    )
    (net (code "79") (name "Net-(Q1-B)") (class "Default")
      (node (ref "C1") (pin "2") (pinfunction "2_2") (pintype "passive"))
      (node (ref "Q1") (pin "1") (pinfunction "B_1") (pintype "passive"))
      (node (ref "R1") (pin "1") (pinfunction "1_1") (pintype "passive"))
    )
    (net (code "80") (name "Net-(Q2-B)") (class "Default")
      (node (ref "C9") (pin "2") (pinfunction "2_2") (pintype "passive"))
      (node (ref "Q2") (pin "1") (pinfunction "B_1") (pintype "passive"))
      (node (ref "R7") (pin "1") (pinfunction "1_1") (pintype "passive"))
    )
    (net (code "81") (name "Net-(Q3-B)") (class "Default")
      (node (ref "Q3") (pin "1") (pinfunction "B_1") (pintype "passive"))
      (node (ref "R19") (pin "2") (pinfunction "2_2") (pintype "passive"))
      (node (ref "R25") (pin "2") (pinfunction "2_2") (pintype "passive"))
    )
    (net (code "82") (name "Net-(Q3-C)") (class "Default")
      (node (ref "Q3") (pin "3") (pinfunction "C_3") (pintype "passive"))
      (node (ref "R15") (pin "1") (pinfunction "1_1") (pintype "passive"))
    )
    (net (code "83") (name "Net-(Q4-B)") (class "Default")
      (node (ref "Q4") (pin "1") (pinfunction "B_1") (pintype "passive"))
      (node (ref "R23") (pin "2") (pinfunction "2_2") (pintype "passive"))
      (node (ref "R27") (pin "2") (pinfunction "2_2") (pintype "passive"))
    )
    (net (code "84") (name "Net-(Q4-C)") (class "Default")
      (node (ref "Q4") (pin "3") (pinfunction "C_3") (pintype "passive"))
      (node (ref "R17") (pin "1") (pinfunction "1_1") (pintype "passive"))
    )
    (net (code "85") (name "Net-(Q5-B)") (class "Default")
      (node (ref "Q5") (pin "1") (pinfunction "B_1") (pintype "passive"))
      (node (ref "R29") (pin "1") (pinfunction "1_1") (pintype "passive"))
      (node (ref "R30") (pin "2") (pinfunction "2_2") (pintype "passive"))
    )
    (net (code "86") (name "Net-(Q6-B)") (class "Default")
      (node (ref "Q6") (pin "1") (pinfunction "B_1") (pintype "passive"))
      (node (ref "R42") (pin "2") (pinfunction "2_2") (pintype "passive"))
      (node (ref "R43") (pin "2") (pinfunction "2_2") (pintype "passive"))
    )
    (net (code "87") (name "Net-(Q6-C)") (class "Default")
      (node (ref "LS1") (pin "M") (pinfunction "M_M") (pintype "passive"))
      (node (ref "Q6") (pin "3") (pinfunction "C_3") (pintype "passive"))
    )
    (net (code "88") (name "Net-(SW1-Pad4)") (class "Default")
      (node (ref "SW1") (pin "4") (pinfunction "4_4") (pintype "passive"))
      (node (ref "SW2") (pin "3") (pinfunction "3_3") (pintype "passive"))
    )
    (net (code "89") (name "Net-(SW2-Pad4)") (class "Default")
      (node (ref "SW2") (pin "4") (pinfunction "4_4") (pintype "passive"))
      (node (ref "SW3") (pin "3") (pinfunction "3_3") (pintype "passive"))
    )
    (net (code "90") (name "Net-(SW3-Pad4)") (class "Default")
      (node (ref "SW3") (pin "4") (pinfunction "4_4") (pintype "passive"))
      (node (ref "SW4") (pin "3") (pinfunction "3_3") (pintype "passive"))
    )
    (net (code "91") (name "Net-(SW5-Pad4)") (class "Default")
      (node (ref "SW5") (pin "4") (pinfunction "4_4") (pintype "passive"))
      (node (ref "SW6") (pin "3") (pinfunction "3_3") (pintype "passive"))
    )
    (net (code "92") (name "Net-(SW6-Pad4)") (class "Default")
      (node (ref "SW6") (pin "4") (pinfunction "4_4") (pintype "passive"))
      (node (ref "SW7") (pin "3") (pinfunction "3_3") (pintype "passive"))
    )
    (net (code "93") (name "Net-(SW7-Pad4)") (class "Default")
      (node (ref "SW7") (pin "4") (pinfunction "4_4") (pintype "passive"))
      (node (ref "SW8") (pin "3") (pinfunction "3_3") (pintype "passive"))
    )
    (net (code "94") (name "Net-(SW10-Pad3)") (class "Default")
      (node (ref "SW10") (pin "3") (pinfunction "3_3") (pintype "passive"))
      (node (ref "SW9") (pin "4") (pinfunction "4_4") (pintype "passive"))
    )
    (net (code "95") (name "Net-(SW10-Pad4)") (class "Default")
      (node (ref "SW10") (pin "4") (pinfunction "4_4") (pintype "passive"))
      (node (ref "SW11") (pin "3") (pinfunction "3_3") (pintype "passive"))
    )
    (net (code "96") (name "Net-(SW11-Pad4)") (class "Default")
      (node (ref "SW11") (pin "4") (pinfunction "4_4") (pintype "passive"))
      (node (ref "SW12") (pin "3") (pinfunction "3_3") (pintype "passive"))
    )
    (net (code "97") (name "Net-(T1-G)") (class "Default")
      (node (ref "R36") (pin "2") (pinfunction "2_2") (pintype "passive"))
      (node (ref "T1") (pin "1") (pinfunction "G_1") (pintype "passive"))
    )
    (net (code "98") (name "Net-(U1-CB)") (class "Default")
      (node (ref "C7") (pin "2") (pinfunction "2_2") (pintype "passive"))
      (node (ref "U1") (pin "1") (pinfunction "CB_1") (pintype "bidirectional"))
    )
    (net (code "99") (name "Net-(U1-FB)") (class "Default")
      (node (ref "R10") (pin "2") (pinfunction "2_2") (pintype "passive"))
      (node (ref "R6") (pin "1") (pinfunction "1_1") (pintype "passive"))
      (node (ref "U1") (pin "3") (pinfunction "FB_3") (pintype "bidirectional"))
    )
    (net (code "100") (name "Net-(U1-SHDN)") (class "Default")
      (node (ref "R3") (pin "1") (pinfunction "1_1") (pintype "passive"))
      (node (ref "U1") (pin "4") (pinfunction "SHDN_4") (pintype "bidirectional"))
    )
    (net (code "101") (name "Net-(U1-SW)") (class "Default")
      (node (ref "C7") (pin "1") (pinfunction "1_1") (pintype "passive"))
      (node (ref "D2") (pin "2") (pinfunction "2_2") (pintype "passive"))
      (node (ref "L2") (pin "1") (pinfunction "1_1") (pintype "passive"))
      (node (ref "U1") (pin "6") (pinfunction "SW_6") (pintype "bidirectional"))
    )
    (net (code "102") (name "Net-(U2-CB)") (class "Default")
      (node (ref "C16") (pin "2") (pinfunction "2_2") (pintype "passive"))
      (node (ref "U2") (pin "1") (pinfunction "CB_1") (pintype "bidirectional"))
    )
    (net (code "103") (name "Net-(U2-FB)") (class "Default")
      (node (ref "R22") (pin "1") (pinfunction "1_1") (pintype "passive"))
      (node (ref "R28") (pin "2") (pinfunction "2_2") (pintype "passive"))
      (node (ref "U2") (pin "3") (pinfunction "FB_3") (pintype "bidirectional"))
    )
    (net (code "104") (name "Net-(U2-SHDN)") (class "Default")
      (node (ref "R20") (pin "1") (pinfunction "1_1") (pintype "passive"))
      (node (ref "U2") (pin "4") (pinfunction "SHDN_4") (pintype "bidirectional"))
    )
    (net (code "105") (name "Net-(U2-SW)") (class "Default")
      (node (ref "C16") (pin "1") (pinfunction "1_1") (pintype "passive"))
      (node (ref "D5") (pin "2") (pinfunction "2_2") (pintype "passive"))
      (node (ref "L3") (pin "1") (pinfunction "1_1") (pintype "passive"))
      (node (ref "U2") (pin "6") (pinfunction "SW_6") (pintype "bidirectional"))
    )
    (net (code "106") (name "Net-(U4-VBAT)") (class "Default")
      (node (ref "RC1") (pin "2") (pinfunction "2_2") (pintype "passive"))
      (node (ref "U4") (pin "1") (pinfunction "VBAT_1") (pintype "bidirectional"))
    )
    (net (code "107") (name "unconnected-(1-PadC4)") (class "Default")
      (node (ref "1") (pin "C4") (pintype "power_in+no_connect"))
    )
    (net (code "108") (name "unconnected-(1-PadC8)") (class "Default")
      (node (ref "1") (pin "C8") (pintype "power_in+no_connect"))
    )
    (net (code "109") (name "unconnected-(1-VPP-PadC6)") (class "Default")
      (node (ref "1") (pin "C6") (pinfunction "VPP_C6") (pintype "power_in+no_connect"))
    )
    (net (code "110") (name "unconnected-(J9-CC1-PadA5)") (class "Default")
      (node (ref "J9") (pin "A5") (pinfunction "CC1_A5") (pintype "bidirectional+no_connect"))
    )
    (net (code "111") (name "unconnected-(J9-CC2-PadB5)") (class "Default")
      (node (ref "J9") (pin "B5") (pinfunction "CC2_B5") (pintype "bidirectional+no_connect"))
    )
    (net (code "112") (name "unconnected-(M1-ADC1-Pad38)") (class "Default")
      (node (ref "M1") (pin "38") (pinfunction "ADC1_38") (pintype "input+no_connect"))
    )
    (net (code "113") (name "unconnected-(M1-CTS-Pad4)") (class "Default")
      (node (ref "M1") (pin "4") (pinfunction "CTS_4") (pintype "output+no_connect"))
    )
    (net (code "114") (name "unconnected-(M1-DBG_RXD-Pad58)") (class "Default")
      (node (ref "M1") (pin "58") (pinfunction "DBG_RXD_58") (pintype "input+no_connect"))
    )
    (net (code "115") (name "unconnected-(M1-DBG_TXD-Pad59)") (class "Default")
      (node (ref "M1") (pin "59") (pinfunction "DBG_TXD_59") (pintype "output+no_connect"))
    )
    (net (code "116") (name "unconnected-(M1-DCD-Pad5)") (class "Default")
      (node (ref "M1") (pin "5") (pinfunction "DCD_5") (pintype "output+no_connect"))
    )
    (net (code "117") (name "unconnected-(M1-DTR-Pad6)") (class "Default")
      (node (ref "M1") (pin "6") (pinfunction "DTR_6") (pintype "input+no_connect"))
    )
    (net (code "118") (name "unconnected-(M1-MIC_N-Pad10)") (class "Default")
      (node (ref "M1") (pin "10") (pinfunction "MIC_N_10") (pintype "passive+no_connect"))
    )
    (net (code "119") (name "unconnected-(M1-MIC_P-Pad9)") (class "Default")
      (node (ref "M1") (pin "9") (pinfunction "MIC_P_9") (pintype "passive+no_connect"))
    )
    (net (code "120") (name "unconnected-(M1-NC-Pad28)") (class "Default")
      (node (ref "M1") (pin "28") (pinfunction "NC_28") (pintype "passive+no_connect"))
    )
    (net (code "121") (name "unconnected-(M1-RESERVED-Pad43)") (class "Default")
      (node (ref "M1") (pin "43") (pinfunction "RESERVED_43") (pintype "passive+no_connect"))
    )
    (net (code "122") (name "unconnected-(M1-RESERVED-Pad44)") (class "Default")
      (node (ref "M1") (pin "44") (pinfunction "RESERVED_44") (pintype "passive+no_connect"))
    )
    (net (code "123") (name "unconnected-(M1-RESERVED-Pad45)") (class "Default")
      (node (ref "M1") (pin "45") (pinfunction "RESERVED_45") (pintype "power_in+no_connect"))
    )
    (net (code "124") (name "unconnected-(M1-RESERVED-Pad46)") (class "Default")
      (node (ref "M1") (pin "46") (pinfunction "RESERVED_46") (pintype "passive+no_connect"))
    )
    (net (code "125") (name "unconnected-(M1-RESERVED-Pad47)") (class "Default")
      (node (ref "M1") (pin "47") (pinfunction "RESERVED_47") (pintype "passive+no_connect"))
    )
    (net (code "126") (name "unconnected-(M1-RESERVED-Pad48)") (class "Default")
      (node (ref "M1") (pin "48") (pinfunction "RESERVED_48") (pintype "passive+no_connect"))
    )
    (net (code "127") (name "unconnected-(M1-RESERVED-Pad49)") (class "Default")
      (node (ref "M1") (pin "49") (pinfunction "RESERVED_49") (pintype "passive+no_connect"))
    )
    (net (code "128") (name "unconnected-(M1-RESERVED-Pad50)") (class "Default")
      (node (ref "M1") (pin "50") (pinfunction "RESERVED_50") (pintype "passive+no_connect"))
    )
    (net (code "129") (name "unconnected-(M1-RESERVED-Pad51)") (class "Default")
      (node (ref "M1") (pin "51") (pinfunction "RESERVED_51") (pintype "passive+no_connect"))
    )
    (net (code "130") (name "unconnected-(M1-RESERVED-Pad52)") (class "Default")
      (node (ref "M1") (pin "52") (pinfunction "RESERVED_52") (pintype "passive+no_connect"))
    )
    (net (code "131") (name "unconnected-(M1-RESERVED-Pad53)") (class "Default")
      (node (ref "M1") (pin "53") (pinfunction "RESERVED_53") (pintype "passive+no_connect"))
    )
    (net (code "132") (name "unconnected-(M1-RESERVED-Pad54)") (class "Default")
      (node (ref "M1") (pin "54") (pinfunction "RESERVED_54") (pintype "passive+no_connect"))
    )
    (net (code "133") (name "unconnected-(M1-RESERVED-Pad55)") (class "Default")
      (node (ref "M1") (pin "55") (pinfunction "RESERVED_55") (pintype "passive+no_connect"))
    )
    (net (code "134") (name "unconnected-(M1-RESERVED-Pad56)") (class "Default")
      (node (ref "M1") (pin "56") (pinfunction "RESERVED_56") (pintype "passive+no_connect"))
    )
    (net (code "135") (name "unconnected-(M1-RESERVED-Pad57)") (class "Default")
      (node (ref "M1") (pin "57") (pinfunction "RESERVED_57") (pintype "passive+no_connect"))
    )
    (net (code "136") (name "unconnected-(M1-RESERVED-Pad60)") (class "Default")
      (node (ref "M1") (pin "60") (pinfunction "RESERVED_60") (pintype "output+no_connect"))
    )
    (net (code "137") (name "unconnected-(M1-RESERVED-Pad61)") (class "Default")
      (node (ref "M1") (pin "61") (pinfunction "RESERVED_61") (pintype "passive+no_connect"))
    )
    (net (code "138") (name "unconnected-(M1-RESERVED-Pad62)") (class "Default")
      (node (ref "M1") (pin "62") (pinfunction "RESERVED_62") (pintype "passive+no_connect"))
    )
    (net (code "139") (name "unconnected-(M1-RESERVED-Pad63)") (class "Default")
      (node (ref "M1") (pin "63") (pinfunction "RESERVED_63") (pintype "passive+no_connect"))
    )
    (net (code "140") (name "unconnected-(M1-RESERVED-Pad64)") (class "Default")
      (node (ref "M1") (pin "64") (pinfunction "RESERVED_64") (pintype "passive+no_connect"))
    )
    (net (code "141") (name "unconnected-(M1-RESERVED-Pad65)") (class "Default")
      (node (ref "M1") (pin "65") (pinfunction "RESERVED_65") (pintype "passive+no_connect"))
    )
    (net (code "142") (name "unconnected-(M1-RESERVED-Pad66)") (class "Default")
      (node (ref "M1") (pin "66") (pinfunction "RESERVED_66") (pintype "input+no_connect"))
    )
    (net (code "143") (name "unconnected-(M1-RESERVED-Pad67)") (class "Default")
      (node (ref "M1") (pin "67") (pinfunction "RESERVED_67") (pintype "power_in+no_connect"))
    )
    (net (code "144") (name "unconnected-(M1-RESERVED-Pad68)") (class "Default")
      (node (ref "M1") (pin "68") (pinfunction "RESERVED_68") (pintype "passive+no_connect"))
    )
    (net (code "145") (name "unconnected-(M1-RESERVED-Pad69)") (class "Default")
      (node (ref "M1") (pin "69") (pinfunction "RESERVED_69") (pintype "passive+no_connect"))
    )
    (net (code "146") (name "unconnected-(M1-RESERVED-Pad70)") (class "Default")
      (node (ref "M1") (pin "70") (pinfunction "RESERVED_70") (pintype "power_in+no_connect"))
    )
    (net (code "147") (name "unconnected-(M1-RESERVED-Pad71)") (class "Default")
      (node (ref "M1") (pin "71") (pinfunction "RESERVED_71") (pintype "power_in+no_connect"))
    )
    (net (code "148") (name "unconnected-(M1-RESERVED-Pad72)") (class "Default")
      (node (ref "M1") (pin "72") (pinfunction "RESERVED_72") (pintype "passive+no_connect"))
    )
    (net (code "149") (name "unconnected-(M1-RESERVED-Pad73)") (class "Default")
      (node (ref "M1") (pin "73") (pinfunction "RESERVED_73") (pintype "passive+no_connect"))
    )
    (net (code "150") (name "unconnected-(M1-RESERVED-Pad74)") (class "Default")
      (node (ref "M1") (pin "74") (pinfunction "RESERVED_74") (pintype "passive+no_connect"))
    )
    (net (code "151") (name "unconnected-(M1-RESERVED-Pad75)") (class "Default")
      (node (ref "M1") (pin "75") (pinfunction "RESERVED_75") (pintype "passive+no_connect"))
    )
    (net (code "152") (name "unconnected-(M1-RESERVED-Pad76)") (class "Default")
      (node (ref "M1") (pin "76") (pinfunction "RESERVED_76") (pintype "passive+no_connect"))
    )
    (net (code "153") (name "unconnected-(M1-RESERVED-Pad77)") (class "Default")
      (node (ref "M1") (pin "77") (pinfunction "RESERVED_77") (pintype "passive+no_connect"))
    )
    (net (code "154") (name "unconnected-(M1-RESERVED-Pad78)") (class "Default")
      (node (ref "M1") (pin "78") (pinfunction "RESERVED_78") (pintype "passive+no_connect"))
    )
    (net (code "155") (name "unconnected-(M1-RESERVED-Pad79)") (class "Default")
      (node (ref "M1") (pin "79") (pinfunction "RESERVED_79") (pintype "passive+no_connect"))
    )
    (net (code "156") (name "unconnected-(M1-RESERVED-Pad80)") (class "Default")
      (node (ref "M1") (pin "80") (pinfunction "RESERVED_80") (pintype "passive+no_connect"))
    )
    (net (code "157") (name "unconnected-(M1-RESERVED-Pad81)") (class "Default")
      (node (ref "M1") (pin "81") (pinfunction "RESERVED_81") (pintype "passive+no_connect"))
    )
    (net (code "158") (name "unconnected-(M1-RESERVED-Pad82)") (class "Default")
      (node (ref "M1") (pin "82") (pinfunction "RESERVED_82") (pintype "passive+no_connect"))
    )
    (net (code "159") (name "unconnected-(M1-RESERVED-Pad83)") (class "Default")
      (node (ref "M1") (pin "83") (pinfunction "RESERVED_83") (pintype "passive+no_connect"))
    )
    (net (code "160") (name "unconnected-(M1-RESERVED-Pad84)") (class "Default")
      (node (ref "M1") (pin "84") (pinfunction "RESERVED_84") (pintype "passive+no_connect"))
    )
    (net (code "161") (name "unconnected-(M1-RESERVED-Pad85)") (class "Default")
      (node (ref "M1") (pin "85") (pinfunction "RESERVED_85") (pintype "passive+no_connect"))
    )
    (net (code "162") (name "unconnected-(M1-RESERVED-Pad86)") (class "Default")
      (node (ref "M1") (pin "86") (pinfunction "RESERVED_86") (pintype "passive+no_connect"))
    )
    (net (code "163") (name "unconnected-(M1-RI-Pad7)") (class "Default")
      (node (ref "M1") (pin "7") (pinfunction "RI_7") (pintype "output+no_connect"))
    )
    (net (code "164") (name "unconnected-(M1-RTS-Pad3)") (class "Default")
      (node (ref "M1") (pin "3") (pinfunction "RTS_3") (pintype "input+no_connect"))
    )
    (net (code "165") (name "unconnected-(M1-SPK_N-Pad12)") (class "Default")
      (node (ref "M1") (pin "12") (pinfunction "SPK_N_12") (pintype "output+no_connect"))
    )
    (net (code "166") (name "unconnected-(M1-SPK_P-Pad11)") (class "Default")
      (node (ref "M1") (pin "11") (pinfunction "SPK_P_11") (pintype "output+no_connect"))
    )
    (net (code "167") (name "unconnected-(M1-UART3_RXD-Pad23)") (class "Default")
      (node (ref "M1") (pin "23") (pinfunction "UART3_RXD_23") (pintype "input+no_connect"))
    )
    (net (code "168") (name "unconnected-(M1-UART3_TXD-Pad22)") (class "Default")
      (node (ref "M1") (pin "22") (pinfunction "UART3_TXD_22") (pintype "output+no_connect"))
    )
    (net (code "169") (name "unconnected-(M1-USB_BOOT-Pad20)") (class "Default")
      (node (ref "M1") (pin "20") (pinfunction "USB_BOOT_20") (pintype "input+no_connect"))
    )
    (net (code "170") (name "unconnected-(M1-USB_DN-Pad26)") (class "Default")
      (node (ref "M1") (pin "26") (pinfunction "USB_DN_26") (pintype "bidirectional+no_connect"))
    )
    (net (code "171") (name "unconnected-(M1-USB_DP-Pad25)") (class "Default")
      (node (ref "M1") (pin "25") (pinfunction "USB_DP_25") (pintype "bidirectional+no_connect"))
    )
    (net (code "172") (name "unconnected-(M1-USB_VBUS-Pad24)") (class "Default")
      (node (ref "M1") (pin "24") (pinfunction "USB_VBUS_24") (pintype "input+no_connect"))
    )
    (net (code "173") (name "unconnected-(SW1-Pad1)") (class "Default")
      (node (ref "SW1") (pin "1") (pinfunction "1_1") (pintype "passive"))
    )
    (net (code "174") (name "unconnected-(SW2-Pad1)") (class "Default")
      (node (ref "SW2") (pin "1") (pinfunction "1_1") (pintype "passive"))
    )
    (net (code "175") (name "unconnected-(SW3-Pad1)") (class "Default")
      (node (ref "SW3") (pin "1") (pinfunction "1_1") (pintype "passive"))
    )
    (net (code "176") (name "unconnected-(SW4-Pad1)") (class "Default")
      (node (ref "SW4") (pin "1") (pinfunction "1_1") (pintype "passive"))
    )
    (net (code "177") (name "unconnected-(SW4-Pad4)") (class "Default")
      (node (ref "SW4") (pin "4") (pinfunction "4_4") (pintype "passive"))
    )
    (net (code "178") (name "unconnected-(SW5-Pad1)") (class "Default")
      (node (ref "SW5") (pin "1") (pinfunction "1_1") (pintype "passive"))
    )
    (net (code "179") (name "unconnected-(SW6-Pad1)") (class "Default")
      (node (ref "SW6") (pin "1") (pinfunction "1_1") (pintype "passive"))
    )
    (net (code "180") (name "unconnected-(SW7-Pad1)") (class "Default")
      (node (ref "SW7") (pin "1") (pinfunction "1_1") (pintype "passive"))
    )
    (net (code "181") (name "unconnected-(SW8-Pad1)") (class "Default")
      (node (ref "SW8") (pin "1") (pinfunction "1_1") (pintype "passive"))
    )
    (net (code "182") (name "unconnected-(SW8-Pad4)") (class "Default")
      (node (ref "SW8") (pin "4") (pinfunction "4_4") (pintype "passive"))
    )
    (net (code "183") (name "unconnected-(SW9-Pad1)") (class "Default")
      (node (ref "SW9") (pin "1") (pinfunction "1_1") (pintype "passive"))
    )
    (net (code "184") (name "unconnected-(SW10-Pad1)") (class "Default")
      (node (ref "SW10") (pin "1") (pinfunction "1_1") (pintype "passive"))
    )
    (net (code "185") (name "unconnected-(SW11-Pad1)") (class "Default")
      (node (ref "SW11") (pin "1") (pinfunction "1_1") (pintype "passive"))
    )
    (net (code "186") (name "unconnected-(SW12-Pad1)") (class "Default")
      (node (ref "SW12") (pin "1") (pinfunction "1_1") (pintype "passive"))
    )
    (net (code "187") (name "unconnected-(SW12-Pad4)") (class "Default")
      (node (ref "SW12") (pin "4") (pinfunction "4_4") (pintype "passive"))
    )
    (net (code "188") (name "unconnected-(SW13-Pad1)") (class "Default")
      (node (ref "SW13") (pin "1") (pinfunction "1_1") (pintype "passive"))
    )
    (net (code "189") (name "unconnected-(SW13-Pad4)") (class "Default")
      (node (ref "SW13") (pin "4") (pinfunction "4_4") (pintype "passive"))
    )
    (net (code "190") (name "unconnected-(U4-PB12-Pad25)") (class "Default")
      (node (ref "U4") (pin "25") (pinfunction "PB12_25") (pintype "bidirectional+no_connect"))
    )
  )
)
